# extio.net
KiCad netlist of a schematic drawn in Altium Designer
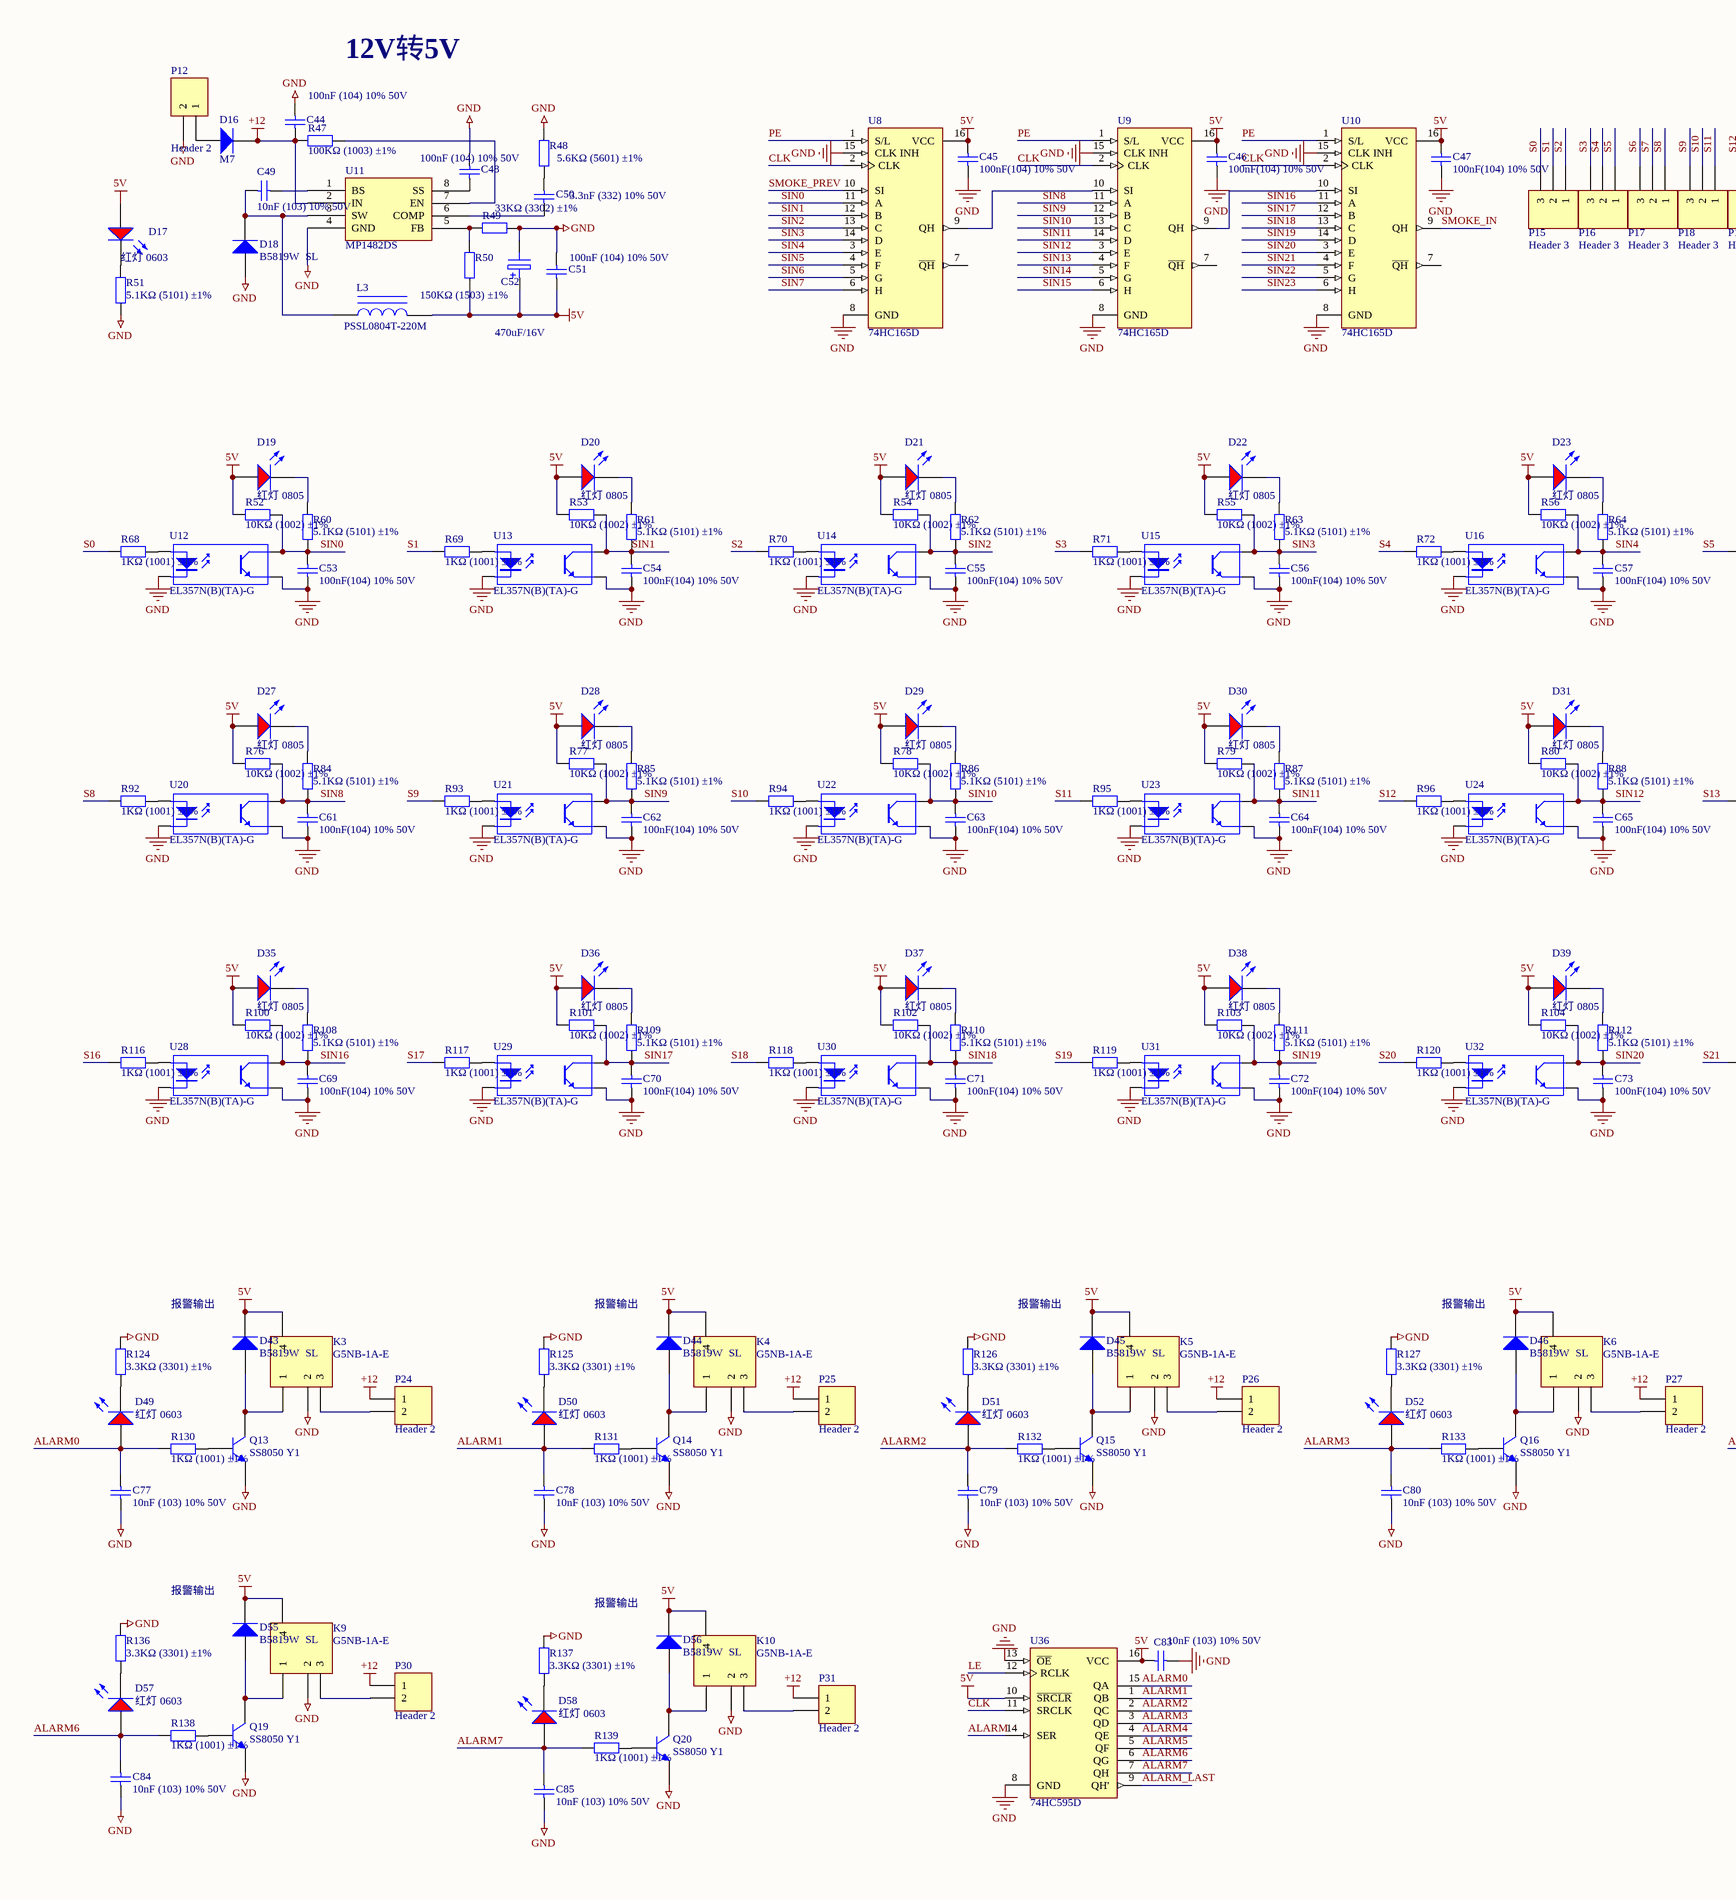
[diagram p0: extio.SchDoc, left]
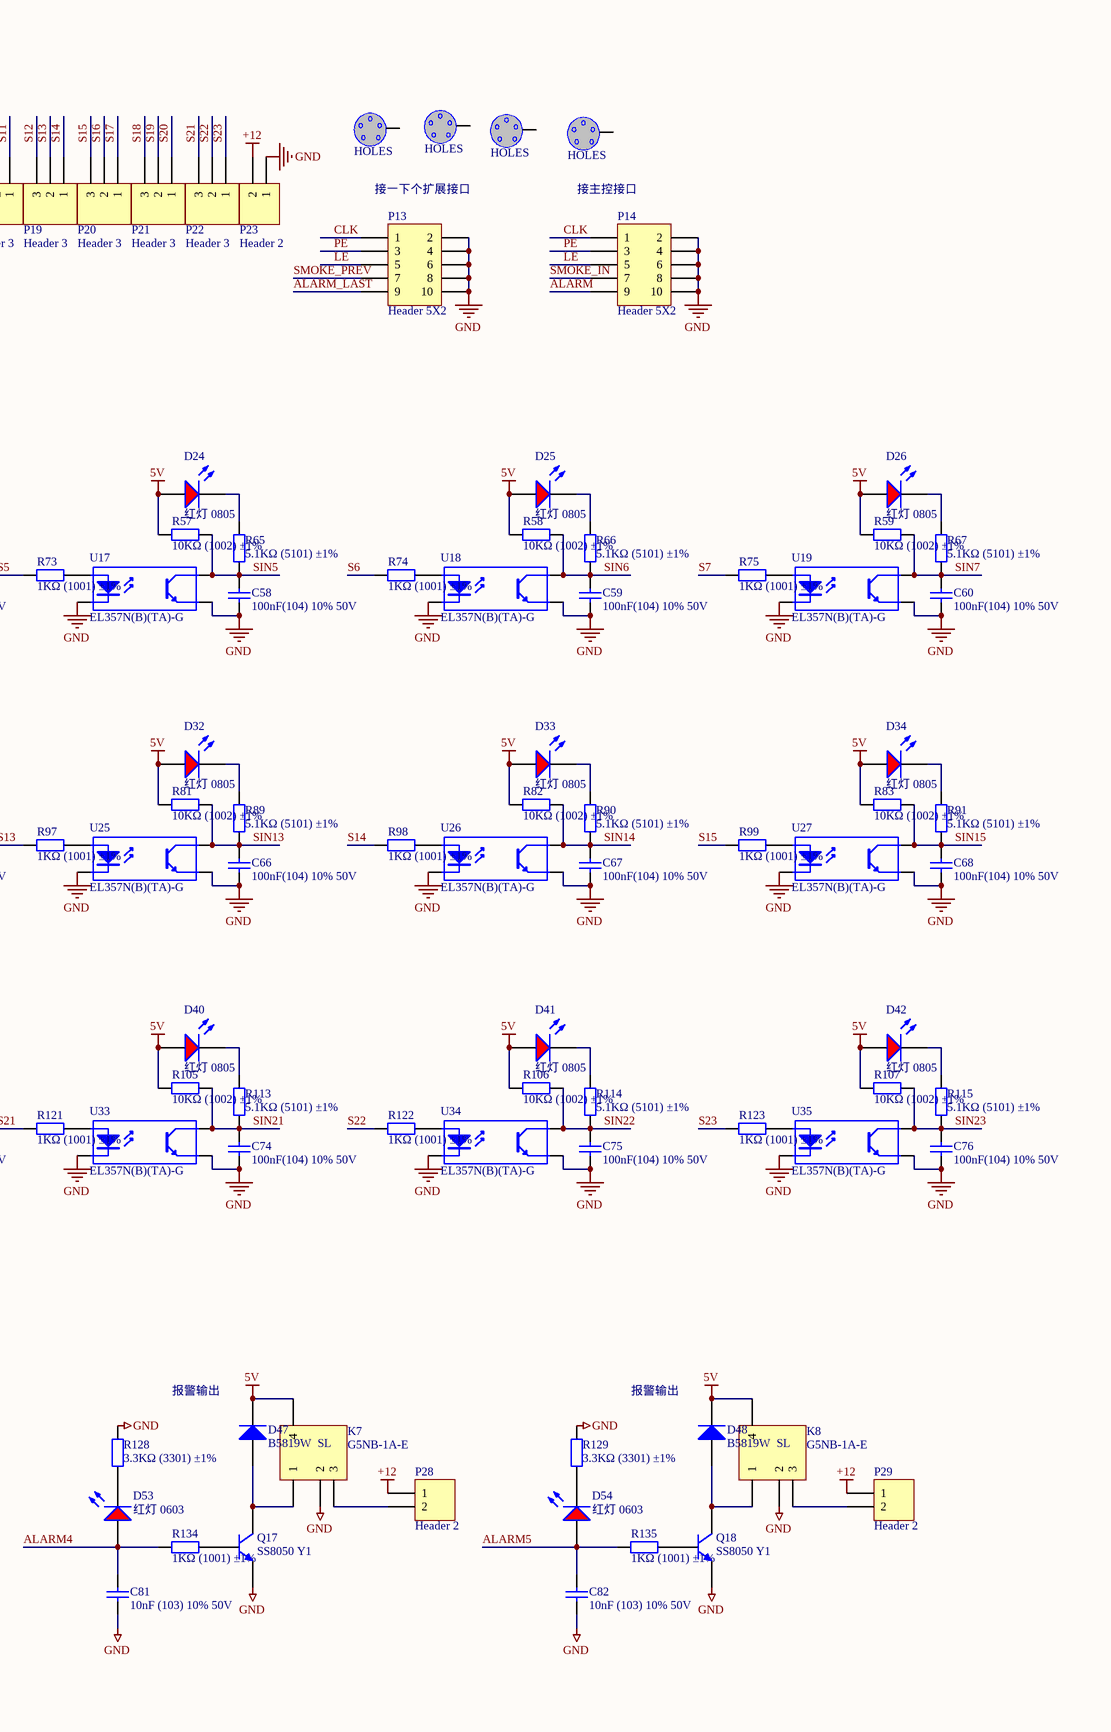
[diagram p1: extio.SchDoc, right]

(export (version "E")
  (design (tool "Eeschema 10.0.6"))
  (components
    (comp (ref "C44")
      (value "100nF (104) 10% 50V")
      (footprint "0603_C")
      (description "贴片电容")
      (libsource (lib "Cap") (part "0603 100nF (104) 10% 50V"))
    )
    (comp (ref "C45")
      (value "100nF(104) 10% 50V")
      (footprint "0805_C")
      (description "贴片电容")
      (libsource (lib "Cap") (part "0805 100nF(104) 10% 50V"))
    )
    (comp (ref "C46")
      (value "100nF(104) 10% 50V")
      (footprint "0805_C")
      (description "贴片电容")
      (libsource (lib "Cap") (part "0805 100nF(104) 10% 50V"))
    )
    (comp (ref "C47")
      (value "100nF(104) 10% 50V")
      (footprint "0805_C")
      (description "贴片电容")
      (libsource (lib "Cap") (part "0805 100nF(104) 10% 50V"))
    )
    (comp (ref "C48")
      (value "100nF (104) 10% 50V")
      (footprint "0603_C")
      (description "贴片电容")
      (libsource (lib "Cap") (part "0603 100nF (104) 10% 50V"))
    )
    (comp (ref "C49")
      (value "10nF (103) 10% 50V")
      (footprint "0603_C")
      (description "贴片电容")
      (libsource (lib "Cap") (part "0603 10nF (103) 10% 50V"))
    )
    (comp (ref "C50")
      (value "3.3nF (332) 10% 50V")
      (footprint "0603_C")
      (description "贴片电容")
      (libsource (lib "Cap") (part "0603 3.3nF (332) 10% 50V"))
    )
    (comp (ref "C51")
      (value "100nF (104) 10% 50V")
      (footprint "0603_C")
      (description "贴片电容")
      (libsource (lib "Cap") (part "0603 100nF (104) 10% 50V"))
    )
    (comp (ref "C52")
      (value "470uF/16V")
      (footprint "153CLV-0810")
      (description "Electrolytic Capacitor")
      (libsource (lib "*") (part "ELECTRO1"))
    )
    (comp (ref "C53")
      (value "100nF(104) 10% 50V")
      (footprint "0805_C")
      (description "贴片电容")
      (libsource (lib "Cap") (part "0805 100nF(104) 10% 50V"))
    )
    (comp (ref "C54")
      (value "100nF(104) 10% 50V")
      (footprint "0805_C")
      (description "贴片电容")
      (libsource (lib "Cap") (part "0805 100nF(104) 10% 50V"))
    )
    (comp (ref "C55")
      (value "100nF(104) 10% 50V")
      (footprint "0805_C")
      (description "贴片电容")
      (libsource (lib "Cap") (part "0805 100nF(104) 10% 50V"))
    )
    (comp (ref "C56")
      (value "100nF(104) 10% 50V")
      (footprint "0805_C")
      (description "贴片电容")
      (libsource (lib "Cap") (part "0805 100nF(104) 10% 50V"))
    )
    (comp (ref "C57")
      (value "100nF(104) 10% 50V")
      (footprint "0805_C")
      (description "贴片电容")
      (libsource (lib "Cap") (part "0805 100nF(104) 10% 50V"))
    )
    (comp (ref "C58")
      (value "100nF(104) 10% 50V")
      (footprint "0805_C")
      (description "贴片电容")
      (libsource (lib "Cap") (part "0805 100nF(104) 10% 50V"))
    )
    (comp (ref "C59")
      (value "100nF(104) 10% 50V")
      (footprint "0805_C")
      (description "贴片电容")
      (libsource (lib "Cap") (part "0805 100nF(104) 10% 50V"))
    )
    (comp (ref "C60")
      (value "100nF(104) 10% 50V")
      (footprint "0805_C")
      (description "贴片电容")
      (libsource (lib "Cap") (part "0805 100nF(104) 10% 50V"))
    )
    (comp (ref "C61")
      (value "100nF(104) 10% 50V")
      (footprint "0805_C")
      (description "贴片电容")
      (libsource (lib "Cap") (part "0805 100nF(104) 10% 50V"))
    )
    (comp (ref "C62")
      (value "100nF(104) 10% 50V")
      (footprint "0805_C")
      (description "贴片电容")
      (libsource (lib "Cap") (part "0805 100nF(104) 10% 50V"))
    )
    (comp (ref "C63")
      (value "100nF(104) 10% 50V")
      (footprint "0805_C")
      (description "贴片电容")
      (libsource (lib "Cap") (part "0805 100nF(104) 10% 50V"))
    )
    (comp (ref "C64")
      (value "100nF(104) 10% 50V")
      (footprint "0805_C")
      (description "贴片电容")
      (libsource (lib "Cap") (part "0805 100nF(104) 10% 50V"))
    )
    (comp (ref "C65")
      (value "100nF(104) 10% 50V")
      (footprint "0805_C")
      (description "贴片电容")
      (libsource (lib "Cap") (part "0805 100nF(104) 10% 50V"))
    )
    (comp (ref "C66")
      (value "100nF(104) 10% 50V")
      (footprint "0805_C")
      (description "贴片电容")
      (libsource (lib "Cap") (part "0805 100nF(104) 10% 50V"))
    )
    (comp (ref "C67")
      (value "100nF(104) 10% 50V")
      (footprint "0805_C")
      (description "贴片电容")
      (libsource (lib "Cap") (part "0805 100nF(104) 10% 50V"))
    )
    (comp (ref "C68")
      (value "100nF(104) 10% 50V")
      (footprint "0805_C")
      (description "贴片电容")
      (libsource (lib "Cap") (part "0805 100nF(104) 10% 50V"))
    )
    (comp (ref "C69")
      (value "100nF(104) 10% 50V")
      (footprint "0805_C")
      (description "贴片电容")
      (libsource (lib "Cap") (part "0805 100nF(104) 10% 50V"))
    )
    (comp (ref "C70")
      (value "100nF(104) 10% 50V")
      (footprint "0805_C")
      (description "贴片电容")
      (libsource (lib "Cap") (part "0805 100nF(104) 10% 50V"))
    )
    (comp (ref "C71")
      (value "100nF(104) 10% 50V")
      (footprint "0805_C")
      (description "贴片电容")
      (libsource (lib "Cap") (part "0805 100nF(104) 10% 50V"))
    )
    (comp (ref "C72")
      (value "100nF(104) 10% 50V")
      (footprint "0805_C")
      (description "贴片电容")
      (libsource (lib "Cap") (part "0805 100nF(104) 10% 50V"))
    )
    (comp (ref "C73")
      (value "100nF(104) 10% 50V")
      (footprint "0805_C")
      (description "贴片电容")
      (libsource (lib "Cap") (part "0805 100nF(104) 10% 50V"))
    )
    (comp (ref "C74")
      (value "100nF(104) 10% 50V")
      (footprint "0805_C")
      (description "贴片电容")
      (libsource (lib "Cap") (part "0805 100nF(104) 10% 50V"))
    )
    (comp (ref "C75")
      (value "100nF(104) 10% 50V")
      (footprint "0805_C")
      (description "贴片电容")
      (libsource (lib "Cap") (part "0805 100nF(104) 10% 50V"))
    )
    (comp (ref "C76")
      (value "100nF(104) 10% 50V")
      (footprint "0805_C")
      (description "贴片电容")
      (libsource (lib "Cap") (part "0805 100nF(104) 10% 50V"))
    )
    (comp (ref "C77")
      (value "10nF (103) 10% 50V")
      (footprint "0603_C")
      (description "贴片电容")
      (libsource (lib "Cap") (part "0603 10nF (103) 10% 50V"))
    )
    (comp (ref "C78")
      (value "10nF (103) 10% 50V")
      (footprint "0603_C")
      (description "贴片电容")
      (libsource (lib "Cap") (part "0603 10nF (103) 10% 50V"))
    )
    (comp (ref "C79")
      (value "10nF (103) 10% 50V")
      (footprint "0603_C")
      (description "贴片电容")
      (libsource (lib "Cap") (part "0603 10nF (103) 10% 50V"))
    )
    (comp (ref "C80")
      (value "10nF (103) 10% 50V")
      (footprint "0603_C")
      (description "贴片电容")
      (libsource (lib "Cap") (part "0603 10nF (103) 10% 50V"))
    )
    (comp (ref "C81")
      (value "10nF (103) 10% 50V")
      (footprint "0603_C")
      (description "贴片电容")
      (libsource (lib "Cap") (part "0603 10nF (103) 10% 50V"))
    )
    (comp (ref "C82")
      (value "10nF (103) 10% 50V")
      (footprint "0603_C")
      (description "贴片电容")
      (libsource (lib "Cap") (part "0603 10nF (103) 10% 50V"))
    )
    (comp (ref "C83")
      (value "10nF (103) 10% 50V")
      (footprint "0603_C")
      (description "贴片电容")
      (libsource (lib "Cap") (part "0603 10nF (103) 10% 50V"))
    )
    (comp (ref "C84")
      (value "10nF (103) 10% 50V")
      (footprint "0603_C")
      (description "贴片电容")
      (libsource (lib "Cap") (part "0603 10nF (103) 10% 50V"))
    )
    (comp (ref "C85")
      (value "10nF (103) 10% 50V")
      (footprint "0603_C")
      (description "贴片电容")
      (libsource (lib "Cap") (part "0603 10nF (103) 10% 50V"))
    )
    (comp (ref "D16")
      (value "M7")
      (footprint "SMA(DO-214AC)_S1")
      (description "二极管")
      (libsource (lib "Diode") (part "SMA(DO-214AC) M7"))
    )
    (comp (ref "D17")
      (value "红灯 0603")
      (footprint "0603_LED_S1")
      (description "发光二极管")
      (libsource (lib "LED") (part "0603 红灯"))
    )
    (comp (ref "D18")
      (value "B5819W  SL")
      (footprint "SOD-123")
      (description "肖特基二极管")
      (libsource (lib "Diode") (part "SOD-123 B5819W  SL"))
    )
    (comp (ref "D19")
      (value "红灯 0805")
      (footprint "0805_LED_S1")
      (description "发光二极管")
      (libsource (lib "LED") (part "0805 红灯"))
    )
    (comp (ref "D20")
      (value "红灯 0805")
      (footprint "0805_LED_S1")
      (description "发光二极管")
      (libsource (lib "LED") (part "0805 红灯"))
    )
    (comp (ref "D21")
      (value "红灯 0805")
      (footprint "0805_LED_S1")
      (description "发光二极管")
      (libsource (lib "LED") (part "0805 红灯"))
    )
    (comp (ref "D22")
      (value "红灯 0805")
      (footprint "0805_LED_S1")
      (description "发光二极管")
      (libsource (lib "LED") (part "0805 红灯"))
    )
    (comp (ref "D23")
      (value "红灯 0805")
      (footprint "0805_LED_S1")
      (description "发光二极管")
      (libsource (lib "LED") (part "0805 红灯"))
    )
    (comp (ref "D24")
      (value "红灯 0805")
      (footprint "0805_LED_S1")
      (description "发光二极管")
      (libsource (lib "LED") (part "0805 红灯"))
    )
    (comp (ref "D25")
      (value "红灯 0805")
      (footprint "0805_LED_S1")
      (description "发光二极管")
      (libsource (lib "LED") (part "0805 红灯"))
    )
    (comp (ref "D26")
      (value "红灯 0805")
      (footprint "0805_LED_S1")
      (description "发光二极管")
      (libsource (lib "LED") (part "0805 红灯"))
    )
    (comp (ref "D27")
      (value "红灯 0805")
      (footprint "0805_LED_S1")
      (description "发光二极管")
      (libsource (lib "LED") (part "0805 红灯"))
    )
    (comp (ref "D28")
      (value "红灯 0805")
      (footprint "0805_LED_S1")
      (description "发光二极管")
      (libsource (lib "LED") (part "0805 红灯"))
    )
    (comp (ref "D29")
      (value "红灯 0805")
      (footprint "0805_LED_S1")
      (description "发光二极管")
      (libsource (lib "LED") (part "0805 红灯"))
    )
    (comp (ref "D30")
      (value "红灯 0805")
      (footprint "0805_LED_S1")
      (description "发光二极管")
      (libsource (lib "LED") (part "0805 红灯"))
    )
    (comp (ref "D31")
      (value "红灯 0805")
      (footprint "0805_LED_S1")
      (description "发光二极管")
      (libsource (lib "LED") (part "0805 红灯"))
    )
    (comp (ref "D32")
      (value "红灯 0805")
      (footprint "0805_LED_S1")
      (description "发光二极管")
      (libsource (lib "LED") (part "0805 红灯"))
    )
    (comp (ref "D33")
      (value "红灯 0805")
      (footprint "0805_LED_S1")
      (description "发光二极管")
      (libsource (lib "LED") (part "0805 红灯"))
    )
    (comp (ref "D34")
      (value "红灯 0805")
      (footprint "0805_LED_S1")
      (description "发光二极管")
      (libsource (lib "LED") (part "0805 红灯"))
    )
    (comp (ref "D35")
      (value "红灯 0805")
      (footprint "0805_LED_S1")
      (description "发光二极管")
      (libsource (lib "LED") (part "0805 红灯"))
    )
    (comp (ref "D36")
      (value "红灯 0805")
      (footprint "0805_LED_S1")
      (description "发光二极管")
      (libsource (lib "LED") (part "0805 红灯"))
    )
    (comp (ref "D37")
      (value "红灯 0805")
      (footprint "0805_LED_S1")
      (description "发光二极管")
      (libsource (lib "LED") (part "0805 红灯"))
    )
    (comp (ref "D38")
      (value "红灯 0805")
      (footprint "0805_LED_S1")
      (description "发光二极管")
      (libsource (lib "LED") (part "0805 红灯"))
    )
    (comp (ref "D39")
      (value "红灯 0805")
      (footprint "0805_LED_S1")
      (description "发光二极管")
      (libsource (lib "LED") (part "0805 红灯"))
    )
    (comp (ref "D40")
      (value "红灯 0805")
      (footprint "0805_LED_S1")
      (description "发光二极管")
      (libsource (lib "LED") (part "0805 红灯"))
    )
    (comp (ref "D41")
      (value "红灯 0805")
      (footprint "0805_LED_S1")
      (description "发光二极管")
      (libsource (lib "LED") (part "0805 红灯"))
    )
    (comp (ref "D42")
      (value "红灯 0805")
      (footprint "0805_LED_S1")
      (description "发光二极管")
      (libsource (lib "LED") (part "0805 红灯"))
    )
    (comp (ref "D43")
      (value "B5819W  SL")
      (footprint "SOD-123")
      (description "肖特基二极管")
      (libsource (lib "Diode") (part "SOD-123 B5819W  SL"))
    )
    (comp (ref "D44")
      (value "B5819W  SL")
      (footprint "SOD-123")
      (description "肖特基二极管")
      (libsource (lib "Diode") (part "SOD-123 B5819W  SL"))
    )
    (comp (ref "D45")
      (value "B5819W  SL")
      (footprint "SOD-123")
      (description "肖特基二极管")
      (libsource (lib "Diode") (part "SOD-123 B5819W  SL"))
    )
    (comp (ref "D46")
      (value "B5819W  SL")
      (footprint "SOD-123")
      (description "肖特基二极管")
      (libsource (lib "Diode") (part "SOD-123 B5819W  SL"))
    )
    (comp (ref "D47")
      (value "B5819W  SL")
      (footprint "SOD-123")
      (description "肖特基二极管")
      (libsource (lib "Diode") (part "SOD-123 B5819W  SL"))
    )
    (comp (ref "D48")
      (value "B5819W  SL")
      (footprint "SOD-123")
      (description "肖特基二极管")
      (libsource (lib "Diode") (part "SOD-123 B5819W  SL"))
    )
    (comp (ref "D49")
      (value "红灯 0603")
      (footprint "0603_LED_S1")
      (description "发光二极管")
      (libsource (lib "LED") (part "0603 红灯"))
    )
    (comp (ref "D50")
      (value "红灯 0603")
      (footprint "0603_LED_S1")
      (description "发光二极管")
      (libsource (lib "LED") (part "0603 红灯"))
    )
    (comp (ref "D51")
      (value "红灯 0603")
      (footprint "0603_LED_S1")
      (description "发光二极管")
      (libsource (lib "LED") (part "0603 红灯"))
    )
    (comp (ref "D52")
      (value "红灯 0603")
      (footprint "0603_LED_S1")
      (description "发光二极管")
      (libsource (lib "LED") (part "0603 红灯"))
    )
    (comp (ref "D53")
      (value "红灯 0603")
      (footprint "0603_LED_S1")
      (description "发光二极管")
      (libsource (lib "LED") (part "0603 红灯"))
    )
    (comp (ref "D54")
      (value "红灯 0603")
      (footprint "0603_LED_S1")
      (description "发光二极管")
      (libsource (lib "LED") (part "0603 红灯"))
    )
    (comp (ref "D55")
      (value "B5819W  SL")
      (footprint "SOD-123")
      (description "肖特基二极管")
      (libsource (lib "Diode") (part "SOD-123 B5819W  SL"))
    )
    (comp (ref "D56")
      (value "B5819W  SL")
      (footprint "SOD-123")
      (description "肖特基二极管")
      (libsource (lib "Diode") (part "SOD-123 B5819W  SL"))
    )
    (comp (ref "D57")
      (value "红灯 0603")
      (footprint "0603_LED_S1")
      (description "发光二极管")
      (libsource (lib "LED") (part "0603 红灯"))
    )
    (comp (ref "D58")
      (value "红灯 0603")
      (footprint "0603_LED_S1")
      (description "发光二极管")
      (libsource (lib "LED") (part "0603 红灯"))
    )
    (comp (ref "HOLES1")
      (value "HOLES")
      (footprint "HOLES")
      (description "holes for fastening")
      (libsource (lib "*") (part "HOLES"))
    )
    (comp (ref "HOLES2")
      (value "HOLES")
      (footprint "HOLES")
      (description "holes for fastening")
      (libsource (lib "*") (part "HOLES"))
    )
    (comp (ref "HOLES3")
      (value "HOLES")
      (footprint "HOLES")
      (description "holes for fastening")
      (libsource (lib "*") (part "HOLES"))
    )
    (comp (ref "HOLES4")
      (value "HOLES")
      (footprint "HOLES")
      (description "holes for fastening")
      (libsource (lib "*") (part "HOLES"))
    )
    (comp (ref "K3") (value "G5NB-1A-E") (footprint "G5NB-1A") (libsource (lib "*") (part "G5NB-1A-E")))
    (comp (ref "K4") (value "G5NB-1A-E") (footprint "G5NB-1A") (libsource (lib "*") (part "G5NB-1A-E")))
    (comp (ref "K5") (value "G5NB-1A-E") (footprint "G5NB-1A") (libsource (lib "*") (part "G5NB-1A-E")))
    (comp (ref "K6") (value "G5NB-1A-E") (footprint "G5NB-1A") (libsource (lib "*") (part "G5NB-1A-E")))
    (comp (ref "K7") (value "G5NB-1A-E") (footprint "G5NB-1A") (libsource (lib "*") (part "G5NB-1A-E")))
    (comp (ref "K8") (value "G5NB-1A-E") (footprint "G5NB-1A") (libsource (lib "*") (part "G5NB-1A-E")))
    (comp (ref "K9") (value "G5NB-1A-E") (footprint "G5NB-1A") (libsource (lib "*") (part "G5NB-1A-E")))
    (comp (ref "K10") (value "G5NB-1A-E") (footprint "G5NB-1A") (libsource (lib "*") (part "G5NB-1A-E")))
    (comp (ref "L3") (value "PSSL0804T-220M") (footprint "L7-8") (libsource (lib "*") (part "INDUCTOR IRON")))
    (comp (ref "P12")
      (value "Header 2")
      (footprint "KF396-2P")
      (description "Header, 2-Pin")
      (fields (field (name "PUBLISHER") "Altium Limited"))
      (libsource (lib "Miscellaneous Connectors") (part "Header 2"))
    )
    (comp (ref "P13")
      (value "Header 5X2")
      (footprint "ML10")
      (description "Header, 5-Pin, Dual row")
      (fields (field (name "PUBLISHER") "Altium Limited"))
      (libsource (lib "Miscellaneous Connectors") (part "Header 5X2"))
    )
    (comp (ref "P14")
      (value "Header 5X2")
      (footprint "ML10")
      (description "Header, 5-Pin, Dual row")
      (fields (field (name "PUBLISHER") "Altium Limited"))
      (libsource (lib "Miscellaneous Connectors") (part "Header 5X2"))
    )
    (comp (ref "P15")
      (value "Header 3")
      (footprint "KF396-3P")
      (description "Header, 3-Pin")
      (fields (field (name "PUBLISHER") "Altium Limited"))
      (libsource (lib "Miscellaneous Connectors") (part "Header 3"))
    )
    (comp (ref "P16")
      (value "Header 3")
      (footprint "KF396-3P")
      (description "Header, 3-Pin")
      (fields (field (name "PUBLISHER") "Altium Limited"))
      (libsource (lib "Miscellaneous Connectors") (part "Header 3"))
    )
    (comp (ref "P17")
      (value "Header 3")
      (footprint "KF396-3P")
      (description "Header, 3-Pin")
      (fields (field (name "PUBLISHER") "Altium Limited"))
      (libsource (lib "Miscellaneous Connectors") (part "Header 3"))
    )
    (comp (ref "P18")
      (value "Header 3")
      (footprint "KF396-3P")
      (description "Header, 3-Pin")
      (fields (field (name "PUBLISHER") "Altium Limited"))
      (libsource (lib "Miscellaneous Connectors") (part "Header 3"))
    )
    (comp (ref "P19")
      (value "Header 3")
      (footprint "KF396-3P")
      (description "Header, 3-Pin")
      (fields (field (name "PUBLISHER") "Altium Limited"))
      (libsource (lib "Miscellaneous Connectors") (part "Header 3"))
    )
    (comp (ref "P20")
      (value "Header 3")
      (footprint "KF396-3P")
      (description "Header, 3-Pin")
      (fields (field (name "PUBLISHER") "Altium Limited"))
      (libsource (lib "Miscellaneous Connectors") (part "Header 3"))
    )
    (comp (ref "P21")
      (value "Header 3")
      (footprint "KF396-3P")
      (description "Header, 3-Pin")
      (fields (field (name "PUBLISHER") "Altium Limited"))
      (libsource (lib "Miscellaneous Connectors") (part "Header 3"))
    )
    (comp (ref "P22")
      (value "Header 3")
      (footprint "KF396-3P")
      (description "Header, 3-Pin")
      (fields (field (name "PUBLISHER") "Altium Limited"))
      (libsource (lib "Miscellaneous Connectors") (part "Header 3"))
    )
    (comp (ref "P23")
      (value "Header 2")
      (footprint "KF396-2P")
      (description "Header, 2-Pin")
      (fields (field (name "PUBLISHER") "Altium Limited"))
      (libsource (lib "") (part "Header 2_1"))
    )
    (comp (ref "P24")
      (value "Header 2")
      (footprint "KF396-2P")
      (description "Header, 2-Pin")
      (fields (field (name "PUBLISHER") "Altium Limited"))
      (libsource (lib "Miscellaneous Connectors") (part "Header 2"))
    )
    (comp (ref "P25")
      (value "Header 2")
      (footprint "KF396-2P")
      (description "Header, 2-Pin")
      (fields (field (name "PUBLISHER") "Altium Limited"))
      (libsource (lib "Miscellaneous Connectors") (part "Header 2"))
    )
    (comp (ref "P26")
      (value "Header 2")
      (footprint "KF396-2P")
      (description "Header, 2-Pin")
      (fields (field (name "PUBLISHER") "Altium Limited"))
      (libsource (lib "Miscellaneous Connectors") (part "Header 2"))
    )
    (comp (ref "P27")
      (value "Header 2")
      (footprint "KF396-2P")
      (description "Header, 2-Pin")
      (fields (field (name "PUBLISHER") "Altium Limited"))
      (libsource (lib "Miscellaneous Connectors") (part "Header 2"))
    )
    (comp (ref "P28")
      (value "Header 2")
      (footprint "KF396-2P")
      (description "Header, 2-Pin")
      (fields (field (name "PUBLISHER") "Altium Limited"))
      (libsource (lib "Miscellaneous Connectors") (part "Header 2"))
    )
    (comp (ref "P29")
      (value "Header 2")
      (footprint "KF396-2P")
      (description "Header, 2-Pin")
      (fields (field (name "PUBLISHER") "Altium Limited"))
      (libsource (lib "Miscellaneous Connectors") (part "Header 2"))
    )
    (comp (ref "P30")
      (value "Header 2")
      (footprint "KF396-2P")
      (description "Header, 2-Pin")
      (fields (field (name "PUBLISHER") "Altium Limited"))
      (libsource (lib "Miscellaneous Connectors") (part "Header 2"))
    )
    (comp (ref "P31")
      (value "Header 2")
      (footprint "KF396-2P")
      (description "Header, 2-Pin")
      (fields (field (name "PUBLISHER") "Altium Limited"))
      (libsource (lib "Miscellaneous Connectors") (part "Header 2"))
    )
    (comp (ref "Q13")
      (value "SS8050 Y1")
      (footprint "SOT-23(SOT-23-3)")
      (description "三极管")
      (libsource (lib "Transistor_NPN") (part "SOT-23 SS8050 Y1"))
    )
    (comp (ref "Q14")
      (value "SS8050 Y1")
      (footprint "SOT-23(SOT-23-3)")
      (description "三极管")
      (libsource (lib "Transistor_NPN") (part "SOT-23 SS8050 Y1"))
    )
    (comp (ref "Q15")
      (value "SS8050 Y1")
      (footprint "SOT-23(SOT-23-3)")
      (description "三极管")
      (libsource (lib "Transistor_NPN") (part "SOT-23 SS8050 Y1"))
    )
    (comp (ref "Q16")
      (value "SS8050 Y1")
      (footprint "SOT-23(SOT-23-3)")
      (description "三极管")
      (libsource (lib "Transistor_NPN") (part "SOT-23 SS8050 Y1"))
    )
    (comp (ref "Q17")
      (value "SS8050 Y1")
      (footprint "SOT-23(SOT-23-3)")
      (description "三极管")
      (libsource (lib "Transistor_NPN") (part "SOT-23 SS8050 Y1"))
    )
    (comp (ref "Q18")
      (value "SS8050 Y1")
      (footprint "SOT-23(SOT-23-3)")
      (description "三极管")
      (libsource (lib "Transistor_NPN") (part "SOT-23 SS8050 Y1"))
    )
    (comp (ref "Q19")
      (value "SS8050 Y1")
      (footprint "SOT-23(SOT-23-3)")
      (description "三极管")
      (libsource (lib "Transistor_NPN") (part "SOT-23 SS8050 Y1"))
    )
    (comp (ref "Q20")
      (value "SS8050 Y1")
      (footprint "SOT-23(SOT-23-3)")
      (description "三极管")
      (libsource (lib "Transistor_NPN") (part "SOT-23 SS8050 Y1"))
    )
    (comp (ref "R47")
      (value "100KΩ (1003) ±1%")
      (footprint "0603_R")
      (description "贴片电阻")
      (libsource (lib "RES") (part "0603 100KΩ (1003) 1%"))
    )
    (comp (ref "R48")
      (value "5.6KΩ (5601) ±1%")
      (footprint "0603_R")
      (description "贴片电阻")
      (libsource (lib "RES") (part "0603 5.6KΩ (5601) 1%"))
    )
    (comp (ref "R49")
      (value "33KΩ (3302) ±1%")
      (footprint "0603_R")
      (description "贴片电阻")
      (libsource (lib "RES") (part "0603 33KΩ (3302) 1%"))
    )
    (comp (ref "R50")
      (value "150KΩ (1503) ±1%")
      (footprint "0603_R")
      (description "贴片电阻")
      (libsource (lib "RES") (part "0603 150KΩ (1503) 1%"))
    )
    (comp (ref "R51")
      (value "5.1KΩ (5101) ±1%")
      (footprint "0805_R")
      (description "贴片电阻")
      (libsource (lib "RES") (part "0805 5.1KΩ (5101) 1%"))
    )
    (comp (ref "R52")
      (value "10KΩ (1002) ±1%")
      (footprint "0805_R")
      (description "贴片电阻")
      (libsource (lib "RES") (part "0805 10KΩ (1002) 1%"))
    )
    (comp (ref "R53")
      (value "10KΩ (1002) ±1%")
      (footprint "0805_R")
      (description "贴片电阻")
      (libsource (lib "RES") (part "0805 10KΩ (1002) 1%"))
    )
    (comp (ref "R54")
      (value "10KΩ (1002) ±1%")
      (footprint "0805_R")
      (description "贴片电阻")
      (libsource (lib "RES") (part "0805 10KΩ (1002) 1%"))
    )
    (comp (ref "R55")
      (value "10KΩ (1002) ±1%")
      (footprint "0805_R")
      (description "贴片电阻")
      (libsource (lib "RES") (part "0805 10KΩ (1002) 1%"))
    )
    (comp (ref "R56")
      (value "10KΩ (1002) ±1%")
      (footprint "0805_R")
      (description "贴片电阻")
      (libsource (lib "RES") (part "0805 10KΩ (1002) 1%"))
    )
    (comp (ref "R57")
      (value "10KΩ (1002) ±1%")
      (footprint "0805_R")
      (description "贴片电阻")
      (libsource (lib "RES") (part "0805 10KΩ (1002) 1%"))
    )
    (comp (ref "R58")
      (value "10KΩ (1002) ±1%")
      (footprint "0805_R")
      (description "贴片电阻")
      (libsource (lib "RES") (part "0805 10KΩ (1002) 1%"))
    )
    (comp (ref "R59")
      (value "10KΩ (1002) ±1%")
      (footprint "0805_R")
      (description "贴片电阻")
      (libsource (lib "RES") (part "0805 10KΩ (1002) 1%"))
    )
    (comp (ref "R60")
      (value "5.1KΩ (5101) ±1%")
      (footprint "0805_R")
      (description "贴片电阻")
      (libsource (lib "RES") (part "0805 5.1KΩ (5101) 1%"))
    )
    (comp (ref "R61")
      (value "5.1KΩ (5101) ±1%")
      (footprint "0805_R")
      (description "贴片电阻")
      (libsource (lib "RES") (part "0805 5.1KΩ (5101) 1%"))
    )
    (comp (ref "R62")
      (value "5.1KΩ (5101) ±1%")
      (footprint "0805_R")
      (description "贴片电阻")
      (libsource (lib "RES") (part "0805 5.1KΩ (5101) 1%"))
    )
    (comp (ref "R63")
      (value "5.1KΩ (5101) ±1%")
      (footprint "0805_R")
      (description "贴片电阻")
      (libsource (lib "RES") (part "0805 5.1KΩ (5101) 1%"))
    )
    (comp (ref "R64")
      (value "5.1KΩ (5101) ±1%")
      (footprint "0805_R")
      (description "贴片电阻")
      (libsource (lib "RES") (part "0805 5.1KΩ (5101) 1%"))
    )
    (comp (ref "R65")
      (value "5.1KΩ (5101) ±1%")
      (footprint "0805_R")
      (description "贴片电阻")
      (libsource (lib "RES") (part "0805 5.1KΩ (5101) 1%"))
    )
    (comp (ref "R66")
      (value "5.1KΩ (5101) ±1%")
      (footprint "0805_R")
      (description "贴片电阻")
      (libsource (lib "RES") (part "0805 5.1KΩ (5101) 1%"))
    )
    (comp (ref "R67")
      (value "5.1KΩ (5101) ±1%")
      (footprint "0805_R")
      (description "贴片电阻")
      (libsource (lib "RES") (part "0805 5.1KΩ (5101) 1%"))
    )
    (comp (ref "R68")
      (value "1KΩ (1001) ±1%")
      (footprint "0805_R")
      (description "贴片电阻")
      (libsource (lib "RES") (part "0805 1KΩ (1001) 1%"))
    )
    (comp (ref "R69")
      (value "1KΩ (1001) ±1%")
      (footprint "0805_R")
      (description "贴片电阻")
      (libsource (lib "RES") (part "0805 1KΩ (1001) 1%"))
    )
    (comp (ref "R70")
      (value "1KΩ (1001) ±1%")
      (footprint "0805_R")
      (description "贴片电阻")
      (libsource (lib "RES") (part "0805 1KΩ (1001) 1%"))
    )
    (comp (ref "R71")
      (value "1KΩ (1001) ±1%")
      (footprint "0805_R")
      (description "贴片电阻")
      (libsource (lib "RES") (part "0805 1KΩ (1001) 1%"))
    )
    (comp (ref "R72")
      (value "1KΩ (1001) ±1%")
      (footprint "0805_R")
      (description "贴片电阻")
      (libsource (lib "RES") (part "0805 1KΩ (1001) 1%"))
    )
    (comp (ref "R73")
      (value "1KΩ (1001) ±1%")
      (footprint "0805_R")
      (description "贴片电阻")
      (libsource (lib "RES") (part "0805 1KΩ (1001) 1%"))
    )
    (comp (ref "R74")
      (value "1KΩ (1001) ±1%")
      (footprint "0805_R")
      (description "贴片电阻")
      (libsource (lib "RES") (part "0805 1KΩ (1001) 1%"))
    )
    (comp (ref "R75")
      (value "1KΩ (1001) ±1%")
      (footprint "0805_R")
      (description "贴片电阻")
      (libsource (lib "RES") (part "0805 1KΩ (1001) 1%"))
    )
    (comp (ref "R76")
      (value "10KΩ (1002) ±1%")
      (footprint "0805_R")
      (description "贴片电阻")
      (libsource (lib "RES") (part "0805 10KΩ (1002) 1%"))
    )
    (comp (ref "R77")
      (value "10KΩ (1002) ±1%")
      (footprint "0805_R")
      (description "贴片电阻")
      (libsource (lib "RES") (part "0805 10KΩ (1002) 1%"))
    )
    (comp (ref "R78")
      (value "10KΩ (1002) ±1%")
      (footprint "0805_R")
      (description "贴片电阻")
      (libsource (lib "RES") (part "0805 10KΩ (1002) 1%"))
    )
    (comp (ref "R79")
      (value "10KΩ (1002) ±1%")
      (footprint "0805_R")
      (description "贴片电阻")
      (libsource (lib "RES") (part "0805 10KΩ (1002) 1%"))
    )
    (comp (ref "R80")
      (value "10KΩ (1002) ±1%")
      (footprint "0805_R")
      (description "贴片电阻")
      (libsource (lib "RES") (part "0805 10KΩ (1002) 1%"))
    )
    (comp (ref "R81")
      (value "10KΩ (1002) ±1%")
      (footprint "0805_R")
      (description "贴片电阻")
      (libsource (lib "RES") (part "0805 10KΩ (1002) 1%"))
    )
    (comp (ref "R82")
      (value "10KΩ (1002) ±1%")
      (footprint "0805_R")
      (description "贴片电阻")
      (libsource (lib "RES") (part "0805 10KΩ (1002) 1%"))
    )
    (comp (ref "R83")
      (value "10KΩ (1002) ±1%")
      (footprint "0805_R")
      (description "贴片电阻")
      (libsource (lib "RES") (part "0805 10KΩ (1002) 1%"))
    )
    (comp (ref "R84")
      (value "5.1KΩ (5101) ±1%")
      (footprint "0805_R")
      (description "贴片电阻")
      (libsource (lib "RES") (part "0805 5.1KΩ (5101) 1%"))
    )
    (comp (ref "R85")
      (value "5.1KΩ (5101) ±1%")
      (footprint "0805_R")
      (description "贴片电阻")
      (libsource (lib "RES") (part "0805 5.1KΩ (5101) 1%"))
    )
    (comp (ref "R86")
      (value "5.1KΩ (5101) ±1%")
      (footprint "0805_R")
      (description "贴片电阻")
      (libsource (lib "RES") (part "0805 5.1KΩ (5101) 1%"))
    )
    (comp (ref "R87")
      (value "5.1KΩ (5101) ±1%")
      (footprint "0805_R")
      (description "贴片电阻")
      (libsource (lib "RES") (part "0805 5.1KΩ (5101) 1%"))
    )
    (comp (ref "R88")
      (value "5.1KΩ (5101) ±1%")
      (footprint "0805_R")
      (description "贴片电阻")
      (libsource (lib "RES") (part "0805 5.1KΩ (5101) 1%"))
    )
    (comp (ref "R89")
      (value "5.1KΩ (5101) ±1%")
      (footprint "0805_R")
      (description "贴片电阻")
      (libsource (lib "RES") (part "0805 5.1KΩ (5101) 1%"))
    )
    (comp (ref "R90")
      (value "5.1KΩ (5101) ±1%")
      (footprint "0805_R")
      (description "贴片电阻")
      (libsource (lib "RES") (part "0805 5.1KΩ (5101) 1%"))
    )
    (comp (ref "R91")
      (value "5.1KΩ (5101) ±1%")
      (footprint "0805_R")
      (description "贴片电阻")
      (libsource (lib "RES") (part "0805 5.1KΩ (5101) 1%"))
    )
    (comp (ref "R92")
      (value "1KΩ (1001) ±1%")
      (footprint "0805_R")
      (description "贴片电阻")
      (libsource (lib "RES") (part "0805 1KΩ (1001) 1%"))
    )
    (comp (ref "R93")
      (value "1KΩ (1001) ±1%")
      (footprint "0805_R")
      (description "贴片电阻")
      (libsource (lib "RES") (part "0805 1KΩ (1001) 1%"))
    )
    (comp (ref "R94")
      (value "1KΩ (1001) ±1%")
      (footprint "0805_R")
      (description "贴片电阻")
      (libsource (lib "RES") (part "0805 1KΩ (1001) 1%"))
    )
    (comp (ref "R95")
      (value "1KΩ (1001) ±1%")
      (footprint "0805_R")
      (description "贴片电阻")
      (libsource (lib "RES") (part "0805 1KΩ (1001) 1%"))
    )
    (comp (ref "R96")
      (value "1KΩ (1001) ±1%")
      (footprint "0805_R")
      (description "贴片电阻")
      (libsource (lib "RES") (part "0805 1KΩ (1001) 1%"))
    )
    (comp (ref "R97")
      (value "1KΩ (1001) ±1%")
      (footprint "0805_R")
      (description "贴片电阻")
      (libsource (lib "RES") (part "0805 1KΩ (1001) 1%"))
    )
    (comp (ref "R98")
      (value "1KΩ (1001) ±1%")
      (footprint "0805_R")
      (description "贴片电阻")
      (libsource (lib "RES") (part "0805 1KΩ (1001) 1%"))
    )
    (comp (ref "R99")
      (value "1KΩ (1001) ±1%")
      (footprint "0805_R")
      (description "贴片电阻")
      (libsource (lib "RES") (part "0805 1KΩ (1001) 1%"))
    )
    (comp (ref "R100")
      (value "10KΩ (1002) ±1%")
      (footprint "0805_R")
      (description "贴片电阻")
      (libsource (lib "RES") (part "0805 10KΩ (1002) 1%"))
    )
    (comp (ref "R101")
      (value "10KΩ (1002) ±1%")
      (footprint "0805_R")
      (description "贴片电阻")
      (libsource (lib "RES") (part "0805 10KΩ (1002) 1%"))
    )
    (comp (ref "R102")
      (value "10KΩ (1002) ±1%")
      (footprint "0805_R")
      (description "贴片电阻")
      (libsource (lib "RES") (part "0805 10KΩ (1002) 1%"))
    )
    (comp (ref "R103")
      (value "10KΩ (1002) ±1%")
      (footprint "0805_R")
      (description "贴片电阻")
      (libsource (lib "RES") (part "0805 10KΩ (1002) 1%"))
    )
    (comp (ref "R104")
      (value "10KΩ (1002) ±1%")
      (footprint "0805_R")
      (description "贴片电阻")
      (libsource (lib "RES") (part "0805 10KΩ (1002) 1%"))
    )
    (comp (ref "R105")
      (value "10KΩ (1002) ±1%")
      (footprint "0805_R")
      (description "贴片电阻")
      (libsource (lib "RES") (part "0805 10KΩ (1002) 1%"))
    )
    (comp (ref "R106")
      (value "10KΩ (1002) ±1%")
      (footprint "0805_R")
      (description "贴片电阻")
      (libsource (lib "RES") (part "0805 10KΩ (1002) 1%"))
    )
    (comp (ref "R107")
      (value "10KΩ (1002) ±1%")
      (footprint "0805_R")
      (description "贴片电阻")
      (libsource (lib "RES") (part "0805 10KΩ (1002) 1%"))
    )
    (comp (ref "R108")
      (value "5.1KΩ (5101) ±1%")
      (footprint "0805_R")
      (description "贴片电阻")
      (libsource (lib "RES") (part "0805 5.1KΩ (5101) 1%"))
    )
    (comp (ref "R109")
      (value "5.1KΩ (5101) ±1%")
      (footprint "0805_R")
      (description "贴片电阻")
      (libsource (lib "RES") (part "0805 5.1KΩ (5101) 1%"))
    )
    (comp (ref "R110")
      (value "5.1KΩ (5101) ±1%")
      (footprint "0805_R")
      (description "贴片电阻")
      (libsource (lib "RES") (part "0805 5.1KΩ (5101) 1%"))
    )
    (comp (ref "R111")
      (value "5.1KΩ (5101) ±1%")
      (footprint "0805_R")
      (description "贴片电阻")
      (libsource (lib "RES") (part "0805 5.1KΩ (5101) 1%"))
    )
    (comp (ref "R112")
      (value "5.1KΩ (5101) ±1%")
      (footprint "0805_R")
      (description "贴片电阻")
      (libsource (lib "RES") (part "0805 5.1KΩ (5101) 1%"))
    )
    (comp (ref "R113")
      (value "5.1KΩ (5101) ±1%")
      (footprint "0805_R")
      (description "贴片电阻")
      (libsource (lib "RES") (part "0805 5.1KΩ (5101) 1%"))
    )
    (comp (ref "R114")
      (value "5.1KΩ (5101) ±1%")
      (footprint "0805_R")
      (description "贴片电阻")
      (libsource (lib "RES") (part "0805 5.1KΩ (5101) 1%"))
    )
    (comp (ref "R115")
      (value "5.1KΩ (5101) ±1%")
      (footprint "0805_R")
      (description "贴片电阻")
      (libsource (lib "RES") (part "0805 5.1KΩ (5101) 1%"))
    )
    (comp (ref "R116")
      (value "1KΩ (1001) ±1%")
      (footprint "0805_R")
      (description "贴片电阻")
      (libsource (lib "RES") (part "0805 1KΩ (1001) 1%"))
    )
    (comp (ref "R117")
      (value "1KΩ (1001) ±1%")
      (footprint "0805_R")
      (description "贴片电阻")
      (libsource (lib "RES") (part "0805 1KΩ (1001) 1%"))
    )
    (comp (ref "R118")
      (value "1KΩ (1001) ±1%")
      (footprint "0805_R")
      (description "贴片电阻")
      (libsource (lib "RES") (part "0805 1KΩ (1001) 1%"))
    )
    (comp (ref "R119")
      (value "1KΩ (1001) ±1%")
      (footprint "0805_R")
      (description "贴片电阻")
      (libsource (lib "RES") (part "0805 1KΩ (1001) 1%"))
    )
    (comp (ref "R120")
      (value "1KΩ (1001) ±1%")
      (footprint "0805_R")
      (description "贴片电阻")
      (libsource (lib "RES") (part "0805 1KΩ (1001) 1%"))
    )
    (comp (ref "R121")
      (value "1KΩ (1001) ±1%")
      (footprint "0805_R")
      (description "贴片电阻")
      (libsource (lib "RES") (part "0805 1KΩ (1001) 1%"))
    )
    (comp (ref "R122")
      (value "1KΩ (1001) ±1%")
      (footprint "0805_R")
      (description "贴片电阻")
      (libsource (lib "RES") (part "0805 1KΩ (1001) 1%"))
    )
    (comp (ref "R123")
      (value "1KΩ (1001) ±1%")
      (footprint "0805_R")
      (description "贴片电阻")
      (libsource (lib "RES") (part "0805 1KΩ (1001) 1%"))
    )
    (comp (ref "R124")
      (value "3.3KΩ (3301) ±1%")
      (footprint "0603_R")
      (description "贴片电阻")
      (libsource (lib "RES") (part "0603 3.3KΩ (3301) 1%"))
    )
    (comp (ref "R125")
      (value "3.3KΩ (3301) ±1%")
      (footprint "0603_R")
      (description "贴片电阻")
      (libsource (lib "RES") (part "0603 3.3KΩ (3301) 1%"))
    )
    (comp (ref "R126")
      (value "3.3KΩ (3301) ±1%")
      (footprint "0603_R")
      (description "贴片电阻")
      (libsource (lib "RES") (part "0603 3.3KΩ (3301) 1%"))
    )
    (comp (ref "R127")
      (value "3.3KΩ (3301) ±1%")
      (footprint "0603_R")
      (description "贴片电阻")
      (libsource (lib "RES") (part "0603 3.3KΩ (3301) 1%"))
    )
    (comp (ref "R128")
      (value "3.3KΩ (3301) ±1%")
      (footprint "0603_R")
      (description "贴片电阻")
      (libsource (lib "RES") (part "0603 3.3KΩ (3301) 1%"))
    )
    (comp (ref "R129")
      (value "3.3KΩ (3301) ±1%")
      (footprint "0603_R")
      (description "贴片电阻")
      (libsource (lib "RES") (part "0603 3.3KΩ (3301) 1%"))
    )
    (comp (ref "R130")
      (value "1KΩ (1001) ±1%")
      (footprint "0603_R")
      (description "贴片电阻")
      (libsource (lib "RES") (part "0603 1KΩ (1001) 1%"))
    )
    (comp (ref "R131")
      (value "1KΩ (1001) ±1%")
      (footprint "0603_R")
      (description "贴片电阻")
      (libsource (lib "RES") (part "0603 1KΩ (1001) 1%"))
    )
    (comp (ref "R132")
      (value "1KΩ (1001) ±1%")
      (footprint "0603_R")
      (description "贴片电阻")
      (libsource (lib "RES") (part "0603 1KΩ (1001) 1%"))
    )
    (comp (ref "R133")
      (value "1KΩ (1001) ±1%")
      (footprint "0603_R")
      (description "贴片电阻")
      (libsource (lib "RES") (part "0603 1KΩ (1001) 1%"))
    )
    (comp (ref "R134")
      (value "1KΩ (1001) ±1%")
      (footprint "0603_R")
      (description "贴片电阻")
      (libsource (lib "RES") (part "0603 1KΩ (1001) 1%"))
    )
    (comp (ref "R135")
      (value "1KΩ (1001) ±1%")
      (footprint "0603_R")
      (description "贴片电阻")
      (libsource (lib "RES") (part "0603 1KΩ (1001) 1%"))
    )
    (comp (ref "R136")
      (value "3.3KΩ (3301) ±1%")
      (footprint "0603_R")
      (description "贴片电阻")
      (libsource (lib "RES") (part "0603 3.3KΩ (3301) 1%"))
    )
    (comp (ref "R137")
      (value "3.3KΩ (3301) ±1%")
      (footprint "0603_R")
      (description "贴片电阻")
      (libsource (lib "RES") (part "0603 3.3KΩ (3301) 1%"))
    )
    (comp (ref "R138")
      (value "1KΩ (1001) ±1%")
      (footprint "0603_R")
      (description "贴片电阻")
      (libsource (lib "RES") (part "0603 1KΩ (1001) 1%"))
    )
    (comp (ref "R139")
      (value "1KΩ (1001) ±1%")
      (footprint "0603_R")
      (description "贴片电阻")
      (libsource (lib "RES") (part "0603 1KΩ (1001) 1%"))
    )
    (comp (ref "U8")
      (value "74HC165D")
      (footprint "SOIC-16_150mil")
      (description "74系列逻辑芯片")
      (libsource (lib "IC") (part "74HC165D_[C5613]"))
    )
    (comp (ref "U9")
      (value "74HC165D")
      (footprint "SOIC-16_150mil")
      (description "74系列逻辑芯片")
      (libsource (lib "IC") (part "74HC165D_[C5613]"))
    )
    (comp (ref "U10")
      (value "74HC165D")
      (footprint "SOIC-16_150mil")
      (description "74系列逻辑芯片")
      (libsource (lib "IC") (part "74HC165D_[C5613]"))
    )
    (comp (ref "U11")
      (value "MP1482DS")
      (footprint "SOIC-8_150mil")
      (description "电源芯片")
      (libsource (lib "IC") (part "MP1482DS_[C14867]"))
    )
    (comp (ref "U12")
      (value "EL357N(B)(TA)-G")
      (footprint "SOP-4_P2.54")
      (description "贴片光耦")
      (libsource (lib "IC") (part "EL357N(B)(TA)-G_[C6649]"))
    )
    (comp (ref "U13")
      (value "EL357N(B)(TA)-G")
      (footprint "SOP-4_P2.54")
      (description "贴片光耦")
      (libsource (lib "IC") (part "EL357N(B)(TA)-G_[C6649]"))
    )
    (comp (ref "U14")
      (value "EL357N(B)(TA)-G")
      (footprint "SOP-4_P2.54")
      (description "贴片光耦")
      (libsource (lib "IC") (part "EL357N(B)(TA)-G_[C6649]"))
    )
    (comp (ref "U15")
      (value "EL357N(B)(TA)-G")
      (footprint "SOP-4_P2.54")
      (description "贴片光耦")
      (libsource (lib "IC") (part "EL357N(B)(TA)-G_[C6649]"))
    )
    (comp (ref "U16")
      (value "EL357N(B)(TA)-G")
      (footprint "SOP-4_P2.54")
      (description "贴片光耦")
      (libsource (lib "IC") (part "EL357N(B)(TA)-G_[C6649]"))
    )
    (comp (ref "U17")
      (value "EL357N(B)(TA)-G")
      (footprint "SOP-4_P2.54")
      (description "贴片光耦")
      (libsource (lib "IC") (part "EL357N(B)(TA)-G_[C6649]"))
    )
    (comp (ref "U18")
      (value "EL357N(B)(TA)-G")
      (footprint "SOP-4_P2.54")
      (description "贴片光耦")
      (libsource (lib "IC") (part "EL357N(B)(TA)-G_[C6649]"))
    )
    (comp (ref "U19")
      (value "EL357N(B)(TA)-G")
      (footprint "SOP-4_P2.54")
      (description "贴片光耦")
      (libsource (lib "IC") (part "EL357N(B)(TA)-G_[C6649]"))
    )
    (comp (ref "U20")
      (value "EL357N(B)(TA)-G")
      (footprint "SOP-4_P2.54")
      (description "贴片光耦")
      (libsource (lib "IC") (part "EL357N(B)(TA)-G_[C6649]"))
    )
    (comp (ref "U21")
      (value "EL357N(B)(TA)-G")
      (footprint "SOP-4_P2.54")
      (description "贴片光耦")
      (libsource (lib "IC") (part "EL357N(B)(TA)-G_[C6649]"))
    )
    (comp (ref "U22")
      (value "EL357N(B)(TA)-G")
      (footprint "SOP-4_P2.54")
      (description "贴片光耦")
      (libsource (lib "IC") (part "EL357N(B)(TA)-G_[C6649]"))
    )
    (comp (ref "U23")
      (value "EL357N(B)(TA)-G")
      (footprint "SOP-4_P2.54")
      (description "贴片光耦")
      (libsource (lib "IC") (part "EL357N(B)(TA)-G_[C6649]"))
    )
    (comp (ref "U24")
      (value "EL357N(B)(TA)-G")
      (footprint "SOP-4_P2.54")
      (description "贴片光耦")
      (libsource (lib "IC") (part "EL357N(B)(TA)-G_[C6649]"))
    )
    (comp (ref "U25")
      (value "EL357N(B)(TA)-G")
      (footprint "SOP-4_P2.54")
      (description "贴片光耦")
      (libsource (lib "IC") (part "EL357N(B)(TA)-G_[C6649]"))
    )
    (comp (ref "U26")
      (value "EL357N(B)(TA)-G")
      (footprint "SOP-4_P2.54")
      (description "贴片光耦")
      (libsource (lib "IC") (part "EL357N(B)(TA)-G_[C6649]"))
    )
    (comp (ref "U27")
      (value "EL357N(B)(TA)-G")
      (footprint "SOP-4_P2.54")
      (description "贴片光耦")
      (libsource (lib "IC") (part "EL357N(B)(TA)-G_[C6649]"))
    )
    (comp (ref "U28")
      (value "EL357N(B)(TA)-G")
      (footprint "SOP-4_P2.54")
      (description "贴片光耦")
      (libsource (lib "IC") (part "EL357N(B)(TA)-G_[C6649]"))
    )
    (comp (ref "U29")
      (value "EL357N(B)(TA)-G")
      (footprint "SOP-4_P2.54")
      (description "贴片光耦")
      (libsource (lib "IC") (part "EL357N(B)(TA)-G_[C6649]"))
    )
    (comp (ref "U30")
      (value "EL357N(B)(TA)-G")
      (footprint "SOP-4_P2.54")
      (description "贴片光耦")
      (libsource (lib "IC") (part "EL357N(B)(TA)-G_[C6649]"))
    )
    (comp (ref "U31")
      (value "EL357N(B)(TA)-G")
      (footprint "SOP-4_P2.54")
      (description "贴片光耦")
      (libsource (lib "IC") (part "EL357N(B)(TA)-G_[C6649]"))
    )
    (comp (ref "U32")
      (value "EL357N(B)(TA)-G")
      (footprint "SOP-4_P2.54")
      (description "贴片光耦")
      (libsource (lib "IC") (part "EL357N(B)(TA)-G_[C6649]"))
    )
    (comp (ref "U33")
      (value "EL357N(B)(TA)-G")
      (footprint "SOP-4_P2.54")
      (description "贴片光耦")
      (libsource (lib "IC") (part "EL357N(B)(TA)-G_[C6649]"))
    )
    (comp (ref "U34")
      (value "EL357N(B)(TA)-G")
      (footprint "SOP-4_P2.54")
      (description "贴片光耦")
      (libsource (lib "IC") (part "EL357N(B)(TA)-G_[C6649]"))
    )
    (comp (ref "U35")
      (value "EL357N(B)(TA)-G")
      (footprint "SOP-4_P2.54")
      (description "贴片光耦")
      (libsource (lib "IC") (part "EL357N(B)(TA)-G_[C6649]"))
    )
    (comp (ref "U36")
      (value "74HC595D")
      (footprint "SOIC-16_150mil")
      (description "74系列逻辑芯片")
      (libsource (lib "IC") (part "74HC595D_[C5947]"))
    )
  )
  (nets
    (net (code "1") (name "+12") (class "Default")
      (node (ref "C44") (pin "2") (pinfunction "2_2") (pintype "passive"))
      (node (ref "D16") (pin "2") (pinfunction "K_2") (pintype "passive"))
      (node (ref "P23") (pin "2") (pinfunction "2_2") (pintype "passive"))
      (node (ref "P24") (pin "1") (pinfunction "1_1") (pintype "passive"))
      (node (ref "P25") (pin "1") (pinfunction "1_1") (pintype "passive"))
      (node (ref "P26") (pin "1") (pinfunction "1_1") (pintype "passive"))
      (node (ref "P27") (pin "1") (pinfunction "1_1") (pintype "passive"))
      (node (ref "P28") (pin "1") (pinfunction "1_1") (pintype "passive"))
      (node (ref "P29") (pin "1") (pinfunction "1_1") (pintype "passive"))
      (node (ref "P30") (pin "1") (pinfunction "1_1") (pintype "passive"))
      (node (ref "P31") (pin "1") (pinfunction "1_1") (pintype "passive"))
      (node (ref "R47") (pin "1") (pinfunction "1_1") (pintype "passive"))
      (node (ref "U11") (pin "2") (pinfunction "IN_2") (pintype "passive"))
    )
    (net (code "3") (name "/ALARM") (class "Default")
      (node (ref "P14") (pin "9") (pinfunction "9_9") (pintype "passive"))
      (node (ref "U36") (pin "14") (pinfunction "SER_14") (pintype "input"))
    )
    (net (code "4") (name "/ALARM0") (class "Default")
      (node (ref "C77") (pin "1") (pinfunction "1_1") (pintype "passive"))
      (node (ref "D49") (pin "A") (pinfunction "A_A") (pintype "passive"))
      (node (ref "R130") (pin "1") (pinfunction "1_1") (pintype "passive"))
      (node (ref "U36") (pin "15") (pinfunction "QA_15") (pintype "tri_state"))
    )
    (net (code "5") (name "/ALARM1") (class "Default")
      (node (ref "C78") (pin "1") (pinfunction "1_1") (pintype "passive"))
      (node (ref "D50") (pin "A") (pinfunction "A_A") (pintype "passive"))
      (node (ref "R131") (pin "1") (pinfunction "1_1") (pintype "passive"))
      (node (ref "U36") (pin "1") (pinfunction "QB_1") (pintype "tri_state"))
    )
    (net (code "6") (name "/ALARM2") (class "Default")
      (node (ref "C79") (pin "1") (pinfunction "1_1") (pintype "passive"))
      (node (ref "D51") (pin "A") (pinfunction "A_A") (pintype "passive"))
      (node (ref "R132") (pin "1") (pinfunction "1_1") (pintype "passive"))
      (node (ref "U36") (pin "2") (pinfunction "QC_2") (pintype "tri_state"))
    )
    (net (code "7") (name "/ALARM3") (class "Default")
      (node (ref "C80") (pin "1") (pinfunction "1_1") (pintype "passive"))
      (node (ref "D52") (pin "A") (pinfunction "A_A") (pintype "passive"))
      (node (ref "R133") (pin "1") (pinfunction "1_1") (pintype "passive"))
      (node (ref "U36") (pin "3") (pinfunction "QD_3") (pintype "tri_state"))
    )
    (net (code "8") (name "/ALARM4") (class "Default")
      (node (ref "C81") (pin "1") (pinfunction "1_1") (pintype "passive"))
      (node (ref "D53") (pin "A") (pinfunction "A_A") (pintype "passive"))
      (node (ref "R134") (pin "1") (pinfunction "1_1") (pintype "passive"))
      (node (ref "U36") (pin "4") (pinfunction "QE_4") (pintype "tri_state"))
    )
    (net (code "9") (name "/ALARM5") (class "Default")
      (node (ref "C82") (pin "1") (pinfunction "1_1") (pintype "passive"))
      (node (ref "D54") (pin "A") (pinfunction "A_A") (pintype "passive"))
      (node (ref "R135") (pin "1") (pinfunction "1_1") (pintype "passive"))
      (node (ref "U36") (pin "5") (pinfunction "QF_5") (pintype "tri_state"))
    )
    (net (code "10") (name "/ALARM6") (class "Default")
      (node (ref "C84") (pin "1") (pinfunction "1_1") (pintype "passive"))
      (node (ref "D57") (pin "A") (pinfunction "A_A") (pintype "passive"))
      (node (ref "R138") (pin "1") (pinfunction "1_1") (pintype "passive"))
      (node (ref "U36") (pin "6") (pinfunction "QG_6") (pintype "tri_state"))
    )
    (net (code "11") (name "/ALARM7") (class "Default")
      (node (ref "C85") (pin "1") (pinfunction "1_1") (pintype "passive"))
      (node (ref "D58") (pin "A") (pinfunction "A_A") (pintype "passive"))
      (node (ref "R139") (pin "1") (pinfunction "1_1") (pintype "passive"))
      (node (ref "U36") (pin "7") (pinfunction "QH_7") (pintype "tri_state"))
    )
    (net (code "12") (name "/ALARM_LAST") (class "Default")
      (node (ref "P13") (pin "9") (pinfunction "9_9") (pintype "passive"))
      (node (ref "U36") (pin "9") (pinfunction "QH'_9") (pintype "output"))
    )
    (net (code "13") (name "/CLK") (class "Default")
      (node (ref "P13") (pin "1") (pinfunction "1_1") (pintype "passive"))
      (node (ref "P14") (pin "1") (pinfunction "1_1") (pintype "passive"))
      (node (ref "U10") (pin "2") (pinfunction "CLK_2") (pintype "input"))
      (node (ref "U36") (pin "11") (pinfunction "SRCLK_11") (pintype "input"))
      (node (ref "U8") (pin "2") (pinfunction "CLK_2") (pintype "input"))
      (node (ref "U9") (pin "2") (pinfunction "CLK_2") (pintype "input"))
    )
    (net (code "14") (name "/LE") (class "Default")
      (node (ref "P13") (pin "5") (pinfunction "5_5") (pintype "passive"))
      (node (ref "P14") (pin "5") (pinfunction "5_5") (pintype "passive"))
      (node (ref "U36") (pin "12") (pinfunction "RCLK_12") (pintype "input"))
    )
    (net (code "15") (name "/PE") (class "Default")
      (node (ref "P13") (pin "3") (pinfunction "3_3") (pintype "passive"))
      (node (ref "P14") (pin "3") (pinfunction "3_3") (pintype "passive"))
      (node (ref "U10") (pin "1") (pinfunction "S/L_1") (pintype "input"))
      (node (ref "U8") (pin "1") (pinfunction "S/L_1") (pintype "input"))
      (node (ref "U9") (pin "1") (pinfunction "S/L_1") (pintype "input"))
    )
    (net (code "16") (name "/S0") (class "Default")
      (node (ref "P15") (pin "3") (pinfunction "3_3") (pintype "passive"))
      (node (ref "R68") (pin "1") (pinfunction "1_1") (pintype "passive"))
    )
    (net (code "17") (name "/S1") (class "Default")
      (node (ref "P15") (pin "2") (pinfunction "2_2") (pintype "passive"))
      (node (ref "R69") (pin "1") (pinfunction "1_1") (pintype "passive"))
    )
    (net (code "18") (name "/S2") (class "Default")
      (node (ref "P15") (pin "1") (pinfunction "1_1") (pintype "passive"))
      (node (ref "R70") (pin "1") (pinfunction "1_1") (pintype "passive"))
    )
    (net (code "19") (name "/S3") (class "Default")
      (node (ref "P16") (pin "3") (pinfunction "3_3") (pintype "passive"))
      (node (ref "R71") (pin "1") (pinfunction "1_1") (pintype "passive"))
    )
    (net (code "20") (name "/S4") (class "Default")
      (node (ref "P16") (pin "2") (pinfunction "2_2") (pintype "passive"))
      (node (ref "R72") (pin "1") (pinfunction "1_1") (pintype "passive"))
    )
    (net (code "21") (name "/S5") (class "Default")
      (node (ref "P16") (pin "1") (pinfunction "1_1") (pintype "passive"))
      (node (ref "R73") (pin "1") (pinfunction "1_1") (pintype "passive"))
    )
    (net (code "22") (name "/S6") (class "Default")
      (node (ref "P17") (pin "3") (pinfunction "3_3") (pintype "passive"))
      (node (ref "R74") (pin "1") (pinfunction "1_1") (pintype "passive"))
    )
    (net (code "23") (name "/S7") (class "Default")
      (node (ref "P17") (pin "2") (pinfunction "2_2") (pintype "passive"))
      (node (ref "R75") (pin "1") (pinfunction "1_1") (pintype "passive"))
    )
    (net (code "24") (name "/S8") (class "Default")
      (node (ref "P17") (pin "1") (pinfunction "1_1") (pintype "passive"))
      (node (ref "R92") (pin "1") (pinfunction "1_1") (pintype "passive"))
    )
    (net (code "25") (name "/S9") (class "Default")
      (node (ref "P18") (pin "3") (pinfunction "3_3") (pintype "passive"))
      (node (ref "R93") (pin "1") (pinfunction "1_1") (pintype "passive"))
    )
    (net (code "26") (name "/S10") (class "Default")
      (node (ref "P18") (pin "2") (pinfunction "2_2") (pintype "passive"))
      (node (ref "R94") (pin "1") (pinfunction "1_1") (pintype "passive"))
    )
    (net (code "27") (name "/S11") (class "Default")
      (node (ref "P18") (pin "1") (pinfunction "1_1") (pintype "passive"))
      (node (ref "R95") (pin "1") (pinfunction "1_1") (pintype "passive"))
    )
    (net (code "28") (name "/S12") (class "Default")
      (node (ref "P19") (pin "3") (pinfunction "3_3") (pintype "passive"))
      (node (ref "R96") (pin "1") (pinfunction "1_1") (pintype "passive"))
    )
    (net (code "29") (name "/S13") (class "Default")
      (node (ref "P19") (pin "2") (pinfunction "2_2") (pintype "passive"))
      (node (ref "R97") (pin "1") (pinfunction "1_1") (pintype "passive"))
    )
    (net (code "30") (name "/S14") (class "Default")
      (node (ref "P19") (pin "1") (pinfunction "1_1") (pintype "passive"))
      (node (ref "R98") (pin "1") (pinfunction "1_1") (pintype "passive"))
    )
    (net (code "31") (name "/S15") (class "Default")
      (node (ref "P20") (pin "3") (pinfunction "3_3") (pintype "passive"))
      (node (ref "R99") (pin "1") (pinfunction "1_1") (pintype "passive"))
    )
    (net (code "32") (name "/S16") (class "Default")
      (node (ref "P20") (pin "2") (pinfunction "2_2") (pintype "passive"))
      (node (ref "R116") (pin "1") (pinfunction "1_1") (pintype "passive"))
    )
    (net (code "33") (name "/S17") (class "Default")
      (node (ref "P20") (pin "1") (pinfunction "1_1") (pintype "passive"))
      (node (ref "R117") (pin "1") (pinfunction "1_1") (pintype "passive"))
    )
    (net (code "34") (name "/S18") (class "Default")
      (node (ref "P21") (pin "3") (pinfunction "3_3") (pintype "passive"))
      (node (ref "R118") (pin "1") (pinfunction "1_1") (pintype "passive"))
    )
    (net (code "35") (name "/S19") (class "Default")
      (node (ref "P21") (pin "2") (pinfunction "2_2") (pintype "passive"))
      (node (ref "R119") (pin "1") (pinfunction "1_1") (pintype "passive"))
    )
    (net (code "36") (name "/S20") (class "Default")
      (node (ref "P21") (pin "1") (pinfunction "1_1") (pintype "passive"))
      (node (ref "R120") (pin "1") (pinfunction "1_1") (pintype "passive"))
    )
    (net (code "37") (name "/S21") (class "Default")
      (node (ref "P22") (pin "3") (pinfunction "3_3") (pintype "passive"))
      (node (ref "R121") (pin "1") (pinfunction "1_1") (pintype "passive"))
    )
    (net (code "38") (name "/S22") (class "Default")
      (node (ref "P22") (pin "2") (pinfunction "2_2") (pintype "passive"))
      (node (ref "R122") (pin "1") (pinfunction "1_1") (pintype "passive"))
    )
    (net (code "39") (name "/S23") (class "Default")
      (node (ref "P22") (pin "1") (pinfunction "1_1") (pintype "passive"))
      (node (ref "R123") (pin "1") (pinfunction "1_1") (pintype "passive"))
    )
    (net (code "40") (name "/SIN0") (class "Default")
      (node (ref "C53") (pin "1") (pinfunction "1_1") (pintype "passive"))
      (node (ref "R52") (pin "1") (pinfunction "1_1") (pintype "passive"))
      (node (ref "R60") (pin "2") (pinfunction "2_2") (pintype "passive"))
      (node (ref "U12") (pin "4") (pinfunction "C_4") (pintype "passive"))
      (node (ref "U8") (pin "11") (pinfunction "A_11") (pintype "input"))
    )
    (net (code "41") (name "/SIN1") (class "Default")
      (node (ref "C54") (pin "1") (pinfunction "1_1") (pintype "passive"))
      (node (ref "R53") (pin "1") (pinfunction "1_1") (pintype "passive"))
      (node (ref "R61") (pin "2") (pinfunction "2_2") (pintype "passive"))
      (node (ref "U13") (pin "4") (pinfunction "C_4") (pintype "passive"))
      (node (ref "U8") (pin "12") (pinfunction "B_12") (pintype "input"))
    )
    (net (code "42") (name "/SIN2") (class "Default")
      (node (ref "C55") (pin "1") (pinfunction "1_1") (pintype "passive"))
      (node (ref "R54") (pin "1") (pinfunction "1_1") (pintype "passive"))
      (node (ref "R62") (pin "2") (pinfunction "2_2") (pintype "passive"))
      (node (ref "U14") (pin "4") (pinfunction "C_4") (pintype "passive"))
      (node (ref "U8") (pin "13") (pinfunction "C_13") (pintype "input"))
    )
    (net (code "43") (name "/SIN3") (class "Default")
      (node (ref "C56") (pin "1") (pinfunction "1_1") (pintype "passive"))
      (node (ref "R55") (pin "1") (pinfunction "1_1") (pintype "passive"))
      (node (ref "R63") (pin "2") (pinfunction "2_2") (pintype "passive"))
      (node (ref "U15") (pin "4") (pinfunction "C_4") (pintype "passive"))
      (node (ref "U8") (pin "14") (pinfunction "D_14") (pintype "input"))
    )
    (net (code "44") (name "/SIN4") (class "Default")
      (node (ref "C57") (pin "1") (pinfunction "1_1") (pintype "passive"))
      (node (ref "R56") (pin "1") (pinfunction "1_1") (pintype "passive"))
      (node (ref "R64") (pin "2") (pinfunction "2_2") (pintype "passive"))
      (node (ref "U16") (pin "4") (pinfunction "C_4") (pintype "passive"))
      (node (ref "U8") (pin "3") (pinfunction "E_3") (pintype "input"))
    )
    (net (code "45") (name "/SIN5") (class "Default")
      (node (ref "C58") (pin "1") (pinfunction "1_1") (pintype "passive"))
      (node (ref "R57") (pin "1") (pinfunction "1_1") (pintype "passive"))
      (node (ref "R65") (pin "2") (pinfunction "2_2") (pintype "passive"))
      (node (ref "U17") (pin "4") (pinfunction "C_4") (pintype "passive"))
      (node (ref "U8") (pin "4") (pinfunction "F_4") (pintype "input"))
    )
    (net (code "46") (name "/SIN6") (class "Default")
      (node (ref "C59") (pin "1") (pinfunction "1_1") (pintype "passive"))
      (node (ref "R58") (pin "1") (pinfunction "1_1") (pintype "passive"))
      (node (ref "R66") (pin "2") (pinfunction "2_2") (pintype "passive"))
      (node (ref "U18") (pin "4") (pinfunction "C_4") (pintype "passive"))
      (node (ref "U8") (pin "5") (pinfunction "G_5") (pintype "input"))
    )
    (net (code "47") (name "/SIN7") (class "Default")
      (node (ref "C60") (pin "1") (pinfunction "1_1") (pintype "passive"))
      (node (ref "R59") (pin "1") (pinfunction "1_1") (pintype "passive"))
      (node (ref "R67") (pin "2") (pinfunction "2_2") (pintype "passive"))
      (node (ref "U19") (pin "4") (pinfunction "C_4") (pintype "passive"))
      (node (ref "U8") (pin "6") (pinfunction "H_6") (pintype "input"))
    )
    (net (code "48") (name "/SIN8") (class "Default")
      (node (ref "C61") (pin "1") (pinfunction "1_1") (pintype "passive"))
      (node (ref "R76") (pin "1") (pinfunction "1_1") (pintype "passive"))
      (node (ref "R84") (pin "2") (pinfunction "2_2") (pintype "passive"))
      (node (ref "U20") (pin "4") (pinfunction "C_4") (pintype "passive"))
      (node (ref "U9") (pin "11") (pinfunction "A_11") (pintype "input"))
    )
    (net (code "49") (name "/SIN9") (class "Default")
      (node (ref "C62") (pin "1") (pinfunction "1_1") (pintype "passive"))
      (node (ref "R77") (pin "1") (pinfunction "1_1") (pintype "passive"))
      (node (ref "R85") (pin "2") (pinfunction "2_2") (pintype "passive"))
      (node (ref "U21") (pin "4") (pinfunction "C_4") (pintype "passive"))
      (node (ref "U9") (pin "12") (pinfunction "B_12") (pintype "input"))
    )
    (net (code "50") (name "/SIN10") (class "Default")
      (node (ref "C63") (pin "1") (pinfunction "1_1") (pintype "passive"))
      (node (ref "R78") (pin "1") (pinfunction "1_1") (pintype "passive"))
      (node (ref "R86") (pin "2") (pinfunction "2_2") (pintype "passive"))
      (node (ref "U22") (pin "4") (pinfunction "C_4") (pintype "passive"))
      (node (ref "U9") (pin "13") (pinfunction "C_13") (pintype "input"))
    )
    (net (code "51") (name "/SIN11") (class "Default")
      (node (ref "C64") (pin "1") (pinfunction "1_1") (pintype "passive"))
      (node (ref "R79") (pin "1") (pinfunction "1_1") (pintype "passive"))
      (node (ref "R87") (pin "2") (pinfunction "2_2") (pintype "passive"))
      (node (ref "U23") (pin "4") (pinfunction "C_4") (pintype "passive"))
      (node (ref "U9") (pin "14") (pinfunction "D_14") (pintype "input"))
    )
    (net (code "52") (name "/SIN12") (class "Default")
      (node (ref "C65") (pin "1") (pinfunction "1_1") (pintype "passive"))
      (node (ref "R80") (pin "1") (pinfunction "1_1") (pintype "passive"))
      (node (ref "R88") (pin "2") (pinfunction "2_2") (pintype "passive"))
      (node (ref "U24") (pin "4") (pinfunction "C_4") (pintype "passive"))
      (node (ref "U9") (pin "3") (pinfunction "E_3") (pintype "input"))
    )
    (net (code "53") (name "/SIN13") (class "Default")
      (node (ref "C66") (pin "1") (pinfunction "1_1") (pintype "passive"))
      (node (ref "R81") (pin "1") (pinfunction "1_1") (pintype "passive"))
      (node (ref "R89") (pin "2") (pinfunction "2_2") (pintype "passive"))
      (node (ref "U25") (pin "4") (pinfunction "C_4") (pintype "passive"))
      (node (ref "U9") (pin "4") (pinfunction "F_4") (pintype "input"))
    )
    (net (code "54") (name "/SIN14") (class "Default")
      (node (ref "C67") (pin "1") (pinfunction "1_1") (pintype "passive"))
      (node (ref "R82") (pin "1") (pinfunction "1_1") (pintype "passive"))
      (node (ref "R90") (pin "2") (pinfunction "2_2") (pintype "passive"))
      (node (ref "U26") (pin "4") (pinfunction "C_4") (pintype "passive"))
      (node (ref "U9") (pin "5") (pinfunction "G_5") (pintype "input"))
    )
    (net (code "55") (name "/SIN15") (class "Default")
      (node (ref "C68") (pin "1") (pinfunction "1_1") (pintype "passive"))
      (node (ref "R83") (pin "1") (pinfunction "1_1") (pintype "passive"))
      (node (ref "R91") (pin "2") (pinfunction "2_2") (pintype "passive"))
      (node (ref "U27") (pin "4") (pinfunction "C_4") (pintype "passive"))
      (node (ref "U9") (pin "6") (pinfunction "H_6") (pintype "input"))
    )
    (net (code "56") (name "/SIN16") (class "Default")
      (node (ref "C69") (pin "1") (pinfunction "1_1") (pintype "passive"))
      (node (ref "R100") (pin "1") (pinfunction "1_1") (pintype "passive"))
      (node (ref "R108") (pin "2") (pinfunction "2_2") (pintype "passive"))
      (node (ref "U10") (pin "11") (pinfunction "A_11") (pintype "input"))
      (node (ref "U28") (pin "4") (pinfunction "C_4") (pintype "passive"))
    )
    (net (code "57") (name "/SIN17") (class "Default")
      (node (ref "C70") (pin "1") (pinfunction "1_1") (pintype "passive"))
      (node (ref "R101") (pin "1") (pinfunction "1_1") (pintype "passive"))
      (node (ref "R109") (pin "2") (pinfunction "2_2") (pintype "passive"))
      (node (ref "U10") (pin "12") (pinfunction "B_12") (pintype "input"))
      (node (ref "U29") (pin "4") (pinfunction "C_4") (pintype "passive"))
    )
    (net (code "58") (name "/SIN18") (class "Default")
      (node (ref "C71") (pin "1") (pinfunction "1_1") (pintype "passive"))
      (node (ref "R102") (pin "1") (pinfunction "1_1") (pintype "passive"))
      (node (ref "R110") (pin "2") (pinfunction "2_2") (pintype "passive"))
      (node (ref "U10") (pin "13") (pinfunction "C_13") (pintype "input"))
      (node (ref "U30") (pin "4") (pinfunction "C_4") (pintype "passive"))
    )
    (net (code "59") (name "/SIN19") (class "Default")
      (node (ref "C72") (pin "1") (pinfunction "1_1") (pintype "passive"))
      (node (ref "R103") (pin "1") (pinfunction "1_1") (pintype "passive"))
      (node (ref "R111") (pin "2") (pinfunction "2_2") (pintype "passive"))
      (node (ref "U10") (pin "14") (pinfunction "D_14") (pintype "input"))
      (node (ref "U31") (pin "4") (pinfunction "C_4") (pintype "passive"))
    )
    (net (code "60") (name "/SIN20") (class "Default")
      (node (ref "C73") (pin "1") (pinfunction "1_1") (pintype "passive"))
      (node (ref "R104") (pin "1") (pinfunction "1_1") (pintype "passive"))
      (node (ref "R112") (pin "2") (pinfunction "2_2") (pintype "passive"))
      (node (ref "U10") (pin "3") (pinfunction "E_3") (pintype "input"))
      (node (ref "U32") (pin "4") (pinfunction "C_4") (pintype "passive"))
    )
    (net (code "61") (name "/SIN21") (class "Default")
      (node (ref "C74") (pin "1") (pinfunction "1_1") (pintype "passive"))
      (node (ref "R105") (pin "1") (pinfunction "1_1") (pintype "passive"))
      (node (ref "R113") (pin "2") (pinfunction "2_2") (pintype "passive"))
      (node (ref "U10") (pin "4") (pinfunction "F_4") (pintype "input"))
      (node (ref "U33") (pin "4") (pinfunction "C_4") (pintype "passive"))
    )
    (net (code "62") (name "/SIN22") (class "Default")
      (node (ref "C75") (pin "1") (pinfunction "1_1") (pintype "passive"))
      (node (ref "R106") (pin "1") (pinfunction "1_1") (pintype "passive"))
      (node (ref "R114") (pin "2") (pinfunction "2_2") (pintype "passive"))
      (node (ref "U10") (pin "5") (pinfunction "G_5") (pintype "input"))
      (node (ref "U34") (pin "4") (pinfunction "C_4") (pintype "passive"))
    )
    (net (code "63") (name "/SIN23") (class "Default")
      (node (ref "C76") (pin "1") (pinfunction "1_1") (pintype "passive"))
      (node (ref "R107") (pin "1") (pinfunction "1_1") (pintype "passive"))
      (node (ref "R115") (pin "2") (pinfunction "2_2") (pintype "passive"))
      (node (ref "U10") (pin "6") (pinfunction "H_6") (pintype "input"))
      (node (ref "U35") (pin "4") (pinfunction "C_4") (pintype "passive"))
    )
    (net (code "64") (name "/SMOKE_IN") (class "Default")
      (node (ref "P14") (pin "7") (pinfunction "7_7") (pintype "passive"))
      (node (ref "U10") (pin "9") (pinfunction "QH_9") (pintype "output"))
    )
    (net (code "65") (name "/SMOKE_PREV") (class "Default")
      (node (ref "P13") (pin "7") (pinfunction "7_7") (pintype "passive"))
      (node (ref "U8") (pin "10") (pinfunction "SI_10") (pintype "input"))
    )
    (net (code "66") (name "5V") (class "Default")
      (node (ref "C45") (pin "1") (pinfunction "1_1") (pintype "passive"))
      (node (ref "C46") (pin "1") (pinfunction "1_1") (pintype "passive"))
      (node (ref "C47") (pin "1") (pinfunction "1_1") (pintype "passive"))
      (node (ref "C51") (pin "1") (pinfunction "1_1") (pintype "passive"))
      (node (ref "C52") (pin "1") (pinfunction "1_1") (pintype "passive"))
      (node (ref "C83") (pin "1") (pinfunction "1_1") (pintype "passive"))
      (node (ref "D17") (pin "A") (pinfunction "A_A") (pintype "passive"))
      (node (ref "D19") (pin "A") (pinfunction "A_A") (pintype "passive"))
      (node (ref "D20") (pin "A") (pinfunction "A_A") (pintype "passive"))
      (node (ref "D21") (pin "A") (pinfunction "A_A") (pintype "passive"))
      (node (ref "D22") (pin "A") (pinfunction "A_A") (pintype "passive"))
      (node (ref "D23") (pin "A") (pinfunction "A_A") (pintype "passive"))
      (node (ref "D24") (pin "A") (pinfunction "A_A") (pintype "passive"))
      (node (ref "D25") (pin "A") (pinfunction "A_A") (pintype "passive"))
      (node (ref "D26") (pin "A") (pinfunction "A_A") (pintype "passive"))
      (node (ref "D27") (pin "A") (pinfunction "A_A") (pintype "passive"))
      (node (ref "D28") (pin "A") (pinfunction "A_A") (pintype "passive"))
      (node (ref "D29") (pin "A") (pinfunction "A_A") (pintype "passive"))
      (node (ref "D30") (pin "A") (pinfunction "A_A") (pintype "passive"))
      (node (ref "D31") (pin "A") (pinfunction "A_A") (pintype "passive"))
      (node (ref "D32") (pin "A") (pinfunction "A_A") (pintype "passive"))
      (node (ref "D33") (pin "A") (pinfunction "A_A") (pintype "passive"))
      (node (ref "D34") (pin "A") (pinfunction "A_A") (pintype "passive"))
      (node (ref "D35") (pin "A") (pinfunction "A_A") (pintype "passive"))
      (node (ref "D36") (pin "A") (pinfunction "A_A") (pintype "passive"))
      (node (ref "D37") (pin "A") (pinfunction "A_A") (pintype "passive"))
      (node (ref "D38") (pin "A") (pinfunction "A_A") (pintype "passive"))
      (node (ref "D39") (pin "A") (pinfunction "A_A") (pintype "passive"))
      (node (ref "D40") (pin "A") (pinfunction "A_A") (pintype "passive"))
      (node (ref "D41") (pin "A") (pinfunction "A_A") (pintype "passive"))
      (node (ref "D42") (pin "A") (pinfunction "A_A") (pintype "passive"))
      (node (ref "D43") (pin "2") (pinfunction "K_2") (pintype "passive"))
      (node (ref "D44") (pin "2") (pinfunction "K_2") (pintype "passive"))
      (node (ref "D45") (pin "2") (pinfunction "K_2") (pintype "passive"))
      (node (ref "D46") (pin "2") (pinfunction "K_2") (pintype "passive"))
      (node (ref "D47") (pin "2") (pinfunction "K_2") (pintype "passive"))
      (node (ref "D48") (pin "2") (pinfunction "K_2") (pintype "passive"))
      (node (ref "D55") (pin "2") (pinfunction "K_2") (pintype "passive"))
      (node (ref "D56") (pin "2") (pinfunction "K_2") (pintype "passive"))
      (node (ref "K10") (pin "4") (pinfunction "4_4") (pintype "passive"))
      (node (ref "K3") (pin "4") (pinfunction "4_4") (pintype "passive"))
      (node (ref "K4") (pin "4") (pinfunction "4_4") (pintype "passive"))
      (node (ref "K5") (pin "4") (pinfunction "4_4") (pintype "passive"))
      (node (ref "K6") (pin "4") (pinfunction "4_4") (pintype "passive"))
      (node (ref "K7") (pin "4") (pinfunction "4_4") (pintype "passive"))
      (node (ref "K8") (pin "4") (pinfunction "4_4") (pintype "passive"))
      (node (ref "K9") (pin "4") (pinfunction "4_4") (pintype "passive"))
      (node (ref "L3") (pin "2") (pinfunction "2_2") (pintype "passive"))
      (node (ref "R100") (pin "2") (pinfunction "2_2") (pintype "passive"))
      (node (ref "R101") (pin "2") (pinfunction "2_2") (pintype "passive"))
      (node (ref "R102") (pin "2") (pinfunction "2_2") (pintype "passive"))
      (node (ref "R103") (pin "2") (pinfunction "2_2") (pintype "passive"))
      (node (ref "R104") (pin "2") (pinfunction "2_2") (pintype "passive"))
      (node (ref "R105") (pin "2") (pinfunction "2_2") (pintype "passive"))
      (node (ref "R106") (pin "2") (pinfunction "2_2") (pintype "passive"))
      (node (ref "R107") (pin "2") (pinfunction "2_2") (pintype "passive"))
      (node (ref "R50") (pin "2") (pinfunction "2_2") (pintype "passive"))
      (node (ref "R52") (pin "2") (pinfunction "2_2") (pintype "passive"))
      (node (ref "R53") (pin "2") (pinfunction "2_2") (pintype "passive"))
      (node (ref "R54") (pin "2") (pinfunction "2_2") (pintype "passive"))
      (node (ref "R55") (pin "2") (pinfunction "2_2") (pintype "passive"))
      (node (ref "R56") (pin "2") (pinfunction "2_2") (pintype "passive"))
      (node (ref "R57") (pin "2") (pinfunction "2_2") (pintype "passive"))
      (node (ref "R58") (pin "2") (pinfunction "2_2") (pintype "passive"))
      (node (ref "R59") (pin "2") (pinfunction "2_2") (pintype "passive"))
      (node (ref "R76") (pin "2") (pinfunction "2_2") (pintype "passive"))
      (node (ref "R77") (pin "2") (pinfunction "2_2") (pintype "passive"))
      (node (ref "R78") (pin "2") (pinfunction "2_2") (pintype "passive"))
      (node (ref "R79") (pin "2") (pinfunction "2_2") (pintype "passive"))
      (node (ref "R80") (pin "2") (pinfunction "2_2") (pintype "passive"))
      (node (ref "R81") (pin "2") (pinfunction "2_2") (pintype "passive"))
      (node (ref "R82") (pin "2") (pinfunction "2_2") (pintype "passive"))
      (node (ref "R83") (pin "2") (pinfunction "2_2") (pintype "passive"))
      (node (ref "U10") (pin "16") (pinfunction "VCC_16") (pintype "power_in"))
      (node (ref "U36") (pin "10") (pinfunction "~{SRCLR}_10") (pintype "input"))
      (node (ref "U36") (pin "16") (pinfunction "VCC_16") (pintype "power_in"))
      (node (ref "U8") (pin "16") (pinfunction "VCC_16") (pintype "power_in"))
      (node (ref "U9") (pin "16") (pinfunction "VCC_16") (pintype "power_in"))
    )
    (net (code "67") (name "GND") (class "Default")
      (node (ref "C44") (pin "1") (pinfunction "1_1") (pintype "passive"))
      (node (ref "C45") (pin "2") (pinfunction "2_2") (pintype "passive"))
      (node (ref "C46") (pin "2") (pinfunction "2_2") (pintype "passive"))
      (node (ref "C47") (pin "2") (pinfunction "2_2") (pintype "passive"))
      (node (ref "C48") (pin "1") (pinfunction "1_1") (pintype "passive"))
      (node (ref "C51") (pin "2") (pinfunction "2_2") (pintype "passive"))
      (node (ref "C52") (pin "2") (pinfunction "2_2") (pintype "passive"))
      (node (ref "C53") (pin "2") (pinfunction "2_2") (pintype "passive"))
      (node (ref "C54") (pin "2") (pinfunction "2_2") (pintype "passive"))
      (node (ref "C55") (pin "2") (pinfunction "2_2") (pintype "passive"))
      (node (ref "C56") (pin "2") (pinfunction "2_2") (pintype "passive"))
      (node (ref "C57") (pin "2") (pinfunction "2_2") (pintype "passive"))
      (node (ref "C58") (pin "2") (pinfunction "2_2") (pintype "passive"))
      (node (ref "C59") (pin "2") (pinfunction "2_2") (pintype "passive"))
      (node (ref "C60") (pin "2") (pinfunction "2_2") (pintype "passive"))
      (node (ref "C61") (pin "2") (pinfunction "2_2") (pintype "passive"))
      (node (ref "C62") (pin "2") (pinfunction "2_2") (pintype "passive"))
      (node (ref "C63") (pin "2") (pinfunction "2_2") (pintype "passive"))
      (node (ref "C64") (pin "2") (pinfunction "2_2") (pintype "passive"))
      (node (ref "C65") (pin "2") (pinfunction "2_2") (pintype "passive"))
      (node (ref "C66") (pin "2") (pinfunction "2_2") (pintype "passive"))
      (node (ref "C67") (pin "2") (pinfunction "2_2") (pintype "passive"))
      (node (ref "C68") (pin "2") (pinfunction "2_2") (pintype "passive"))
      (node (ref "C69") (pin "2") (pinfunction "2_2") (pintype "passive"))
      (node (ref "C70") (pin "2") (pinfunction "2_2") (pintype "passive"))
      (node (ref "C71") (pin "2") (pinfunction "2_2") (pintype "passive"))
      (node (ref "C72") (pin "2") (pinfunction "2_2") (pintype "passive"))
      (node (ref "C73") (pin "2") (pinfunction "2_2") (pintype "passive"))
      (node (ref "C74") (pin "2") (pinfunction "2_2") (pintype "passive"))
      (node (ref "C75") (pin "2") (pinfunction "2_2") (pintype "passive"))
      (node (ref "C76") (pin "2") (pinfunction "2_2") (pintype "passive"))
      (node (ref "C77") (pin "2") (pinfunction "2_2") (pintype "passive"))
      (node (ref "C78") (pin "2") (pinfunction "2_2") (pintype "passive"))
      (node (ref "C79") (pin "2") (pinfunction "2_2") (pintype "passive"))
      (node (ref "C80") (pin "2") (pinfunction "2_2") (pintype "passive"))
      (node (ref "C81") (pin "2") (pinfunction "2_2") (pintype "passive"))
      (node (ref "C82") (pin "2") (pinfunction "2_2") (pintype "passive"))
      (node (ref "C83") (pin "2") (pinfunction "2_2") (pintype "passive"))
      (node (ref "C84") (pin "2") (pinfunction "2_2") (pintype "passive"))
      (node (ref "C85") (pin "2") (pinfunction "2_2") (pintype "passive"))
      (node (ref "D18") (pin "1") (pinfunction "A_1") (pintype "passive"))
      (node (ref "K10") (pin "2") (pinfunction "2_2") (pintype "passive"))
      (node (ref "K3") (pin "2") (pinfunction "2_2") (pintype "passive"))
      (node (ref "K4") (pin "2") (pinfunction "2_2") (pintype "passive"))
      (node (ref "K5") (pin "2") (pinfunction "2_2") (pintype "passive"))
      (node (ref "K6") (pin "2") (pinfunction "2_2") (pintype "passive"))
      (node (ref "K7") (pin "2") (pinfunction "2_2") (pintype "passive"))
      (node (ref "K8") (pin "2") (pinfunction "2_2") (pintype "passive"))
      (node (ref "K9") (pin "2") (pinfunction "2_2") (pintype "passive"))
      (node (ref "P12") (pin "2") (pinfunction "2_2") (pintype "passive"))
      (node (ref "P13") (pin "10") (pinfunction "10_10") (pintype "passive"))
      (node (ref "P13") (pin "2") (pinfunction "2_2") (pintype "passive"))
      (node (ref "P13") (pin "4") (pinfunction "4_4") (pintype "passive"))
      (node (ref "P13") (pin "6") (pinfunction "6_6") (pintype "passive"))
      (node (ref "P13") (pin "8") (pinfunction "8_8") (pintype "passive"))
      (node (ref "P14") (pin "10") (pinfunction "10_10") (pintype "passive"))
      (node (ref "P14") (pin "2") (pinfunction "2_2") (pintype "passive"))
      (node (ref "P14") (pin "4") (pinfunction "4_4") (pintype "passive"))
      (node (ref "P14") (pin "6") (pinfunction "6_6") (pintype "passive"))
      (node (ref "P14") (pin "8") (pinfunction "8_8") (pintype "passive"))
      (node (ref "P23") (pin "1") (pinfunction "1_1") (pintype "passive"))
      (node (ref "Q13") (pin "2") (pinfunction "E_2") (pintype "passive"))
      (node (ref "Q14") (pin "2") (pinfunction "E_2") (pintype "passive"))
      (node (ref "Q15") (pin "2") (pinfunction "E_2") (pintype "passive"))
      (node (ref "Q16") (pin "2") (pinfunction "E_2") (pintype "passive"))
      (node (ref "Q17") (pin "2") (pinfunction "E_2") (pintype "passive"))
      (node (ref "Q18") (pin "2") (pinfunction "E_2") (pintype "passive"))
      (node (ref "Q19") (pin "2") (pinfunction "E_2") (pintype "passive"))
      (node (ref "Q20") (pin "2") (pinfunction "E_2") (pintype "passive"))
      (node (ref "R124") (pin "1") (pinfunction "1_1") (pintype "passive"))
      (node (ref "R125") (pin "1") (pinfunction "1_1") (pintype "passive"))
      (node (ref "R126") (pin "1") (pinfunction "1_1") (pintype "passive"))
      (node (ref "R127") (pin "1") (pinfunction "1_1") (pintype "passive"))
      (node (ref "R128") (pin "1") (pinfunction "1_1") (pintype "passive"))
      (node (ref "R129") (pin "1") (pinfunction "1_1") (pintype "passive"))
      (node (ref "R136") (pin "1") (pinfunction "1_1") (pintype "passive"))
      (node (ref "R137") (pin "1") (pinfunction "1_1") (pintype "passive"))
      (node (ref "R48") (pin "2") (pinfunction "2_2") (pintype "passive"))
      (node (ref "R49") (pin "2") (pinfunction "2_2") (pintype "passive"))
      (node (ref "R51") (pin "2") (pinfunction "2_2") (pintype "passive"))
      (node (ref "U10") (pin "15") (pinfunction "CLK_INH_15") (pintype "input"))
      (node (ref "U10") (pin "8") (pinfunction "GND_8") (pintype "power_in"))
      (node (ref "U11") (pin "4") (pinfunction "GND_4") (pintype "passive"))
      (node (ref "U12") (pin "2") (pinfunction "K_2") (pintype "passive"))
      (node (ref "U12") (pin "3") (pinfunction "E_3") (pintype "passive"))
      (node (ref "U13") (pin "2") (pinfunction "K_2") (pintype "passive"))
      (node (ref "U13") (pin "3") (pinfunction "E_3") (pintype "passive"))
      (node (ref "U14") (pin "2") (pinfunction "K_2") (pintype "passive"))
      (node (ref "U14") (pin "3") (pinfunction "E_3") (pintype "passive"))
      (node (ref "U15") (pin "2") (pinfunction "K_2") (pintype "passive"))
      (node (ref "U15") (pin "3") (pinfunction "E_3") (pintype "passive"))
      (node (ref "U16") (pin "2") (pinfunction "K_2") (pintype "passive"))
      (node (ref "U16") (pin "3") (pinfunction "E_3") (pintype "passive"))
      (node (ref "U17") (pin "2") (pinfunction "K_2") (pintype "passive"))
      (node (ref "U17") (pin "3") (pinfunction "E_3") (pintype "passive"))
      (node (ref "U18") (pin "2") (pinfunction "K_2") (pintype "passive"))
      (node (ref "U18") (pin "3") (pinfunction "E_3") (pintype "passive"))
      (node (ref "U19") (pin "2") (pinfunction "K_2") (pintype "passive"))
      (node (ref "U19") (pin "3") (pinfunction "E_3") (pintype "passive"))
      (node (ref "U20") (pin "2") (pinfunction "K_2") (pintype "passive"))
      (node (ref "U20") (pin "3") (pinfunction "E_3") (pintype "passive"))
      (node (ref "U21") (pin "2") (pinfunction "K_2") (pintype "passive"))
      (node (ref "U21") (pin "3") (pinfunction "E_3") (pintype "passive"))
      (node (ref "U22") (pin "2") (pinfunction "K_2") (pintype "passive"))
      (node (ref "U22") (pin "3") (pinfunction "E_3") (pintype "passive"))
      (node (ref "U23") (pin "2") (pinfunction "K_2") (pintype "passive"))
      (node (ref "U23") (pin "3") (pinfunction "E_3") (pintype "passive"))
      (node (ref "U24") (pin "2") (pinfunction "K_2") (pintype "passive"))
      (node (ref "U24") (pin "3") (pinfunction "E_3") (pintype "passive"))
      (node (ref "U25") (pin "2") (pinfunction "K_2") (pintype "passive"))
      (node (ref "U25") (pin "3") (pinfunction "E_3") (pintype "passive"))
      (node (ref "U26") (pin "2") (pinfunction "K_2") (pintype "passive"))
      (node (ref "U26") (pin "3") (pinfunction "E_3") (pintype "passive"))
      (node (ref "U27") (pin "2") (pinfunction "K_2") (pintype "passive"))
      (node (ref "U27") (pin "3") (pinfunction "E_3") (pintype "passive"))
      (node (ref "U28") (pin "2") (pinfunction "K_2") (pintype "passive"))
      (node (ref "U28") (pin "3") (pinfunction "E_3") (pintype "passive"))
      (node (ref "U29") (pin "2") (pinfunction "K_2") (pintype "passive"))
      (node (ref "U29") (pin "3") (pinfunction "E_3") (pintype "passive"))
      (node (ref "U30") (pin "2") (pinfunction "K_2") (pintype "passive"))
      (node (ref "U30") (pin "3") (pinfunction "E_3") (pintype "passive"))
      (node (ref "U31") (pin "2") (pinfunction "K_2") (pintype "passive"))
      (node (ref "U31") (pin "3") (pinfunction "E_3") (pintype "passive"))
      (node (ref "U32") (pin "2") (pinfunction "K_2") (pintype "passive"))
      (node (ref "U32") (pin "3") (pinfunction "E_3") (pintype "passive"))
      (node (ref "U33") (pin "2") (pinfunction "K_2") (pintype "passive"))
      (node (ref "U33") (pin "3") (pinfunction "E_3") (pintype "passive"))
      (node (ref "U34") (pin "2") (pinfunction "K_2") (pintype "passive"))
      (node (ref "U34") (pin "3") (pinfunction "E_3") (pintype "passive"))
      (node (ref "U35") (pin "2") (pinfunction "K_2") (pintype "passive"))
      (node (ref "U35") (pin "3") (pinfunction "E_3") (pintype "passive"))
      (node (ref "U36") (pin "13") (pinfunction "~{OE}_13") (pintype "input"))
      (node (ref "U36") (pin "8") (pinfunction "GND_8") (pintype "power_in"))
      (node (ref "U8") (pin "15") (pinfunction "CLK_INH_15") (pintype "input"))
      (node (ref "U8") (pin "8") (pinfunction "GND_8") (pintype "power_in"))
      (node (ref "U9") (pin "15") (pinfunction "CLK_INH_15") (pintype "input"))
      (node (ref "U9") (pin "8") (pinfunction "GND_8") (pintype "power_in"))
    )
    (net (code "68") (name "Net-(C50-Pad1)") (class "Default")
      (node (ref "C50") (pin "1") (pinfunction "1_1") (pintype "passive"))
      (node (ref "R48") (pin "1") (pinfunction "1_1") (pintype "passive"))
    )
    (net (code "69") (name "Net-(D16-A)") (class "Default")
      (node (ref "D16") (pin "1") (pinfunction "A_1") (pintype "passive"))
      (node (ref "P12") (pin "1") (pinfunction "1_1") (pintype "passive"))
    )
    (net (code "70") (name "Net-(D17-PadK)") (class "Default")
      (node (ref "D17") (pin "K") (pinfunction "K_K") (pintype "passive"))
      (node (ref "R51") (pin "1") (pinfunction "1_1") (pintype "passive"))
    )
    (net (code "71") (name "Net-(D18-K)") (class "Default")
      (node (ref "C49") (pin "1") (pinfunction "1_1") (pintype "passive"))
      (node (ref "D18") (pin "2") (pinfunction "K_2") (pintype "passive"))
      (node (ref "L3") (pin "1") (pinfunction "1_1") (pintype "passive"))
      (node (ref "U11") (pin "3") (pinfunction "SW_3") (pintype "passive"))
    )
    (net (code "72") (name "Net-(D19-PadK)") (class "Default")
      (node (ref "D19") (pin "K") (pinfunction "K_K") (pintype "passive"))
      (node (ref "R60") (pin "1") (pinfunction "1_1") (pintype "passive"))
    )
    (net (code "73") (name "Net-(D20-PadK)") (class "Default")
      (node (ref "D20") (pin "K") (pinfunction "K_K") (pintype "passive"))
      (node (ref "R61") (pin "1") (pinfunction "1_1") (pintype "passive"))
    )
    (net (code "74") (name "Net-(D21-PadK)") (class "Default")
      (node (ref "D21") (pin "K") (pinfunction "K_K") (pintype "passive"))
      (node (ref "R62") (pin "1") (pinfunction "1_1") (pintype "passive"))
    )
    (net (code "75") (name "Net-(D22-PadK)") (class "Default")
      (node (ref "D22") (pin "K") (pinfunction "K_K") (pintype "passive"))
      (node (ref "R63") (pin "1") (pinfunction "1_1") (pintype "passive"))
    )
    (net (code "76") (name "Net-(D23-PadK)") (class "Default")
      (node (ref "D23") (pin "K") (pinfunction "K_K") (pintype "passive"))
      (node (ref "R64") (pin "1") (pinfunction "1_1") (pintype "passive"))
    )
    (net (code "77") (name "Net-(D24-PadK)") (class "Default")
      (node (ref "D24") (pin "K") (pinfunction "K_K") (pintype "passive"))
      (node (ref "R65") (pin "1") (pinfunction "1_1") (pintype "passive"))
    )
    (net (code "78") (name "Net-(D25-PadK)") (class "Default")
      (node (ref "D25") (pin "K") (pinfunction "K_K") (pintype "passive"))
      (node (ref "R66") (pin "1") (pinfunction "1_1") (pintype "passive"))
    )
    (net (code "79") (name "Net-(D26-PadK)") (class "Default")
      (node (ref "D26") (pin "K") (pinfunction "K_K") (pintype "passive"))
      (node (ref "R67") (pin "1") (pinfunction "1_1") (pintype "passive"))
    )
    (net (code "80") (name "Net-(D27-PadK)") (class "Default")
      (node (ref "D27") (pin "K") (pinfunction "K_K") (pintype "passive"))
      (node (ref "R84") (pin "1") (pinfunction "1_1") (pintype "passive"))
    )
    (net (code "81") (name "Net-(D28-PadK)") (class "Default")
      (node (ref "D28") (pin "K") (pinfunction "K_K") (pintype "passive"))
      (node (ref "R85") (pin "1") (pinfunction "1_1") (pintype "passive"))
    )
    (net (code "82") (name "Net-(D29-PadK)") (class "Default")
      (node (ref "D29") (pin "K") (pinfunction "K_K") (pintype "passive"))
      (node (ref "R86") (pin "1") (pinfunction "1_1") (pintype "passive"))
    )
    (net (code "83") (name "Net-(D30-PadK)") (class "Default")
      (node (ref "D30") (pin "K") (pinfunction "K_K") (pintype "passive"))
      (node (ref "R87") (pin "1") (pinfunction "1_1") (pintype "passive"))
    )
    (net (code "84") (name "Net-(D31-PadK)") (class "Default")
      (node (ref "D31") (pin "K") (pinfunction "K_K") (pintype "passive"))
      (node (ref "R88") (pin "1") (pinfunction "1_1") (pintype "passive"))
    )
    (net (code "85") (name "Net-(D32-PadK)") (class "Default")
      (node (ref "D32") (pin "K") (pinfunction "K_K") (pintype "passive"))
      (node (ref "R89") (pin "1") (pinfunction "1_1") (pintype "passive"))
    )
    (net (code "86") (name "Net-(D33-PadK)") (class "Default")
      (node (ref "D33") (pin "K") (pinfunction "K_K") (pintype "passive"))
      (node (ref "R90") (pin "1") (pinfunction "1_1") (pintype "passive"))
    )
    (net (code "87") (name "Net-(D34-PadK)") (class "Default")
      (node (ref "D34") (pin "K") (pinfunction "K_K") (pintype "passive"))
      (node (ref "R91") (pin "1") (pinfunction "1_1") (pintype "passive"))
    )
    (net (code "88") (name "Net-(D35-PadK)") (class "Default")
      (node (ref "D35") (pin "K") (pinfunction "K_K") (pintype "passive"))
      (node (ref "R108") (pin "1") (pinfunction "1_1") (pintype "passive"))
    )
    (net (code "89") (name "Net-(D36-PadK)") (class "Default")
      (node (ref "D36") (pin "K") (pinfunction "K_K") (pintype "passive"))
      (node (ref "R109") (pin "1") (pinfunction "1_1") (pintype "passive"))
    )
    (net (code "90") (name "Net-(D37-PadK)") (class "Default")
      (node (ref "D37") (pin "K") (pinfunction "K_K") (pintype "passive"))
      (node (ref "R110") (pin "1") (pinfunction "1_1") (pintype "passive"))
    )
    (net (code "91") (name "Net-(D38-PadK)") (class "Default")
      (node (ref "D38") (pin "K") (pinfunction "K_K") (pintype "passive"))
      (node (ref "R111") (pin "1") (pinfunction "1_1") (pintype "passive"))
    )
    (net (code "92") (name "Net-(D39-PadK)") (class "Default")
      (node (ref "D39") (pin "K") (pinfunction "K_K") (pintype "passive"))
      (node (ref "R112") (pin "1") (pinfunction "1_1") (pintype "passive"))
    )
    (net (code "93") (name "Net-(D40-PadK)") (class "Default")
      (node (ref "D40") (pin "K") (pinfunction "K_K") (pintype "passive"))
      (node (ref "R113") (pin "1") (pinfunction "1_1") (pintype "passive"))
    )
    (net (code "94") (name "Net-(D41-PadK)") (class "Default")
      (node (ref "D41") (pin "K") (pinfunction "K_K") (pintype "passive"))
      (node (ref "R114") (pin "1") (pinfunction "1_1") (pintype "passive"))
    )
    (net (code "95") (name "Net-(D42-PadK)") (class "Default")
      (node (ref "D42") (pin "K") (pinfunction "K_K") (pintype "passive"))
      (node (ref "R115") (pin "1") (pinfunction "1_1") (pintype "passive"))
    )
    (net (code "96") (name "Net-(D43-A)") (class "Default")
      (node (ref "D43") (pin "1") (pinfunction "A_1") (pintype "passive"))
      (node (ref "K3") (pin "1") (pinfunction "1_1") (pintype "passive"))
      (node (ref "Q13") (pin "3") (pinfunction "C_3") (pintype "passive"))
    )
    (net (code "97") (name "Net-(D44-A)") (class "Default")
      (node (ref "D44") (pin "1") (pinfunction "A_1") (pintype "passive"))
      (node (ref "K4") (pin "1") (pinfunction "1_1") (pintype "passive"))
      (node (ref "Q14") (pin "3") (pinfunction "C_3") (pintype "passive"))
    )
    (net (code "98") (name "Net-(D45-A)") (class "Default")
      (node (ref "D45") (pin "1") (pinfunction "A_1") (pintype "passive"))
      (node (ref "K5") (pin "1") (pinfunction "1_1") (pintype "passive"))
      (node (ref "Q15") (pin "3") (pinfunction "C_3") (pintype "passive"))
    )
    (net (code "99") (name "Net-(D46-A)") (class "Default")
      (node (ref "D46") (pin "1") (pinfunction "A_1") (pintype "passive"))
      (node (ref "K6") (pin "1") (pinfunction "1_1") (pintype "passive"))
      (node (ref "Q16") (pin "3") (pinfunction "C_3") (pintype "passive"))
    )
    (net (code "100") (name "Net-(D47-A)") (class "Default")
      (node (ref "D47") (pin "1") (pinfunction "A_1") (pintype "passive"))
      (node (ref "K7") (pin "1") (pinfunction "1_1") (pintype "passive"))
      (node (ref "Q17") (pin "3") (pinfunction "C_3") (pintype "passive"))
    )
    (net (code "101") (name "Net-(D48-A)") (class "Default")
      (node (ref "D48") (pin "1") (pinfunction "A_1") (pintype "passive"))
      (node (ref "K8") (pin "1") (pinfunction "1_1") (pintype "passive"))
      (node (ref "Q18") (pin "3") (pinfunction "C_3") (pintype "passive"))
    )
    (net (code "102") (name "Net-(D49-PadK)") (class "Default")
      (node (ref "D49") (pin "K") (pinfunction "K_K") (pintype "passive"))
      (node (ref "R124") (pin "2") (pinfunction "2_2") (pintype "passive"))
    )
    (net (code "103") (name "Net-(D50-PadK)") (class "Default")
      (node (ref "D50") (pin "K") (pinfunction "K_K") (pintype "passive"))
      (node (ref "R125") (pin "2") (pinfunction "2_2") (pintype "passive"))
    )
    (net (code "104") (name "Net-(D51-PadK)") (class "Default")
      (node (ref "D51") (pin "K") (pinfunction "K_K") (pintype "passive"))
      (node (ref "R126") (pin "2") (pinfunction "2_2") (pintype "passive"))
    )
    (net (code "105") (name "Net-(D52-PadK)") (class "Default")
      (node (ref "D52") (pin "K") (pinfunction "K_K") (pintype "passive"))
      (node (ref "R127") (pin "2") (pinfunction "2_2") (pintype "passive"))
    )
    (net (code "106") (name "Net-(D53-PadK)") (class "Default")
      (node (ref "D53") (pin "K") (pinfunction "K_K") (pintype "passive"))
      (node (ref "R128") (pin "2") (pinfunction "2_2") (pintype "passive"))
    )
    (net (code "107") (name "Net-(D54-PadK)") (class "Default")
      (node (ref "D54") (pin "K") (pinfunction "K_K") (pintype "passive"))
      (node (ref "R129") (pin "2") (pinfunction "2_2") (pintype "passive"))
    )
    (net (code "108") (name "Net-(D55-A)") (class "Default")
      (node (ref "D55") (pin "1") (pinfunction "A_1") (pintype "passive"))
      (node (ref "K9") (pin "1") (pinfunction "1_1") (pintype "passive"))
      (node (ref "Q19") (pin "3") (pinfunction "C_3") (pintype "passive"))
    )
    (net (code "109") (name "Net-(D56-A)") (class "Default")
      (node (ref "D56") (pin "1") (pinfunction "A_1") (pintype "passive"))
      (node (ref "K10") (pin "1") (pinfunction "1_1") (pintype "passive"))
      (node (ref "Q20") (pin "3") (pinfunction "C_3") (pintype "passive"))
    )
    (net (code "110") (name "Net-(D57-PadK)") (class "Default")
      (node (ref "D57") (pin "K") (pinfunction "K_K") (pintype "passive"))
      (node (ref "R136") (pin "2") (pinfunction "2_2") (pintype "passive"))
    )
    (net (code "111") (name "Net-(D58-PadK)") (class "Default")
      (node (ref "D58") (pin "K") (pinfunction "K_K") (pintype "passive"))
      (node (ref "R137") (pin "2") (pinfunction "2_2") (pintype "passive"))
    )
    (net (code "112") (name "Net-(K3-Pad3)") (class "Default")
      (node (ref "K3") (pin "3") (pinfunction "3_3") (pintype "passive"))
      (node (ref "P24") (pin "2") (pinfunction "2_2") (pintype "passive"))
    )
    (net (code "113") (name "Net-(K4-Pad3)") (class "Default")
      (node (ref "K4") (pin "3") (pinfunction "3_3") (pintype "passive"))
      (node (ref "P25") (pin "2") (pinfunction "2_2") (pintype "passive"))
    )
    (net (code "114") (name "Net-(K5-Pad3)") (class "Default")
      (node (ref "K5") (pin "3") (pinfunction "3_3") (pintype "passive"))
      (node (ref "P26") (pin "2") (pinfunction "2_2") (pintype "passive"))
    )
    (net (code "115") (name "Net-(K6-Pad3)") (class "Default")
      (node (ref "K6") (pin "3") (pinfunction "3_3") (pintype "passive"))
      (node (ref "P27") (pin "2") (pinfunction "2_2") (pintype "passive"))
    )
    (net (code "116") (name "Net-(K7-Pad3)") (class "Default")
      (node (ref "K7") (pin "3") (pinfunction "3_3") (pintype "passive"))
      (node (ref "P28") (pin "2") (pinfunction "2_2") (pintype "passive"))
    )
    (net (code "117") (name "Net-(K8-Pad3)") (class "Default")
      (node (ref "K8") (pin "3") (pinfunction "3_3") (pintype "passive"))
      (node (ref "P29") (pin "2") (pinfunction "2_2") (pintype "passive"))
    )
    (net (code "118") (name "Net-(K9-Pad3)") (class "Default")
      (node (ref "K9") (pin "3") (pinfunction "3_3") (pintype "passive"))
      (node (ref "P30") (pin "2") (pinfunction "2_2") (pintype "passive"))
    )
    (net (code "119") (name "Net-(K10-Pad3)") (class "Default")
      (node (ref "K10") (pin "3") (pinfunction "3_3") (pintype "passive"))
      (node (ref "P31") (pin "2") (pinfunction "2_2") (pintype "passive"))
    )
    (net (code "120") (name "Net-(Q13-B)") (class "Default")
      (node (ref "Q13") (pin "1") (pinfunction "B_1") (pintype "passive"))
      (node (ref "R130") (pin "2") (pinfunction "2_2") (pintype "passive"))
    )
    (net (code "121") (name "Net-(Q14-B)") (class "Default")
      (node (ref "Q14") (pin "1") (pinfunction "B_1") (pintype "passive"))
      (node (ref "R131") (pin "2") (pinfunction "2_2") (pintype "passive"))
    )
    (net (code "122") (name "Net-(Q15-B)") (class "Default")
      (node (ref "Q15") (pin "1") (pinfunction "B_1") (pintype "passive"))
      (node (ref "R132") (pin "2") (pinfunction "2_2") (pintype "passive"))
    )
    (net (code "123") (name "Net-(Q16-B)") (class "Default")
      (node (ref "Q16") (pin "1") (pinfunction "B_1") (pintype "passive"))
      (node (ref "R133") (pin "2") (pinfunction "2_2") (pintype "passive"))
    )
    (net (code "124") (name "Net-(Q17-B)") (class "Default")
      (node (ref "Q17") (pin "1") (pinfunction "B_1") (pintype "passive"))
      (node (ref "R134") (pin "2") (pinfunction "2_2") (pintype "passive"))
    )
    (net (code "125") (name "Net-(Q18-B)") (class "Default")
      (node (ref "Q18") (pin "1") (pinfunction "B_1") (pintype "passive"))
      (node (ref "R135") (pin "2") (pinfunction "2_2") (pintype "passive"))
    )
    (net (code "126") (name "Net-(Q19-B)") (class "Default")
      (node (ref "Q19") (pin "1") (pinfunction "B_1") (pintype "passive"))
      (node (ref "R138") (pin "2") (pinfunction "2_2") (pintype "passive"))
    )
    (net (code "127") (name "Net-(Q20-B)") (class "Default")
      (node (ref "Q20") (pin "1") (pinfunction "B_1") (pintype "passive"))
      (node (ref "R139") (pin "2") (pinfunction "2_2") (pintype "passive"))
    )
    (net (code "128") (name "Net-(U8-QH)") (class "Default")
      (node (ref "U8") (pin "9") (pinfunction "QH_9") (pintype "output"))
      (node (ref "U9") (pin "10") (pinfunction "SI_10") (pintype "input"))
    )
    (net (code "129") (name "Net-(U10-SI)") (class "Default")
      (node (ref "U10") (pin "10") (pinfunction "SI_10") (pintype "input"))
      (node (ref "U9") (pin "9") (pinfunction "QH_9") (pintype "output"))
    )
    (net (code "130") (name "Net-(U11-BS)") (class "Default")
      (node (ref "C49") (pin "2") (pinfunction "2_2") (pintype "passive"))
      (node (ref "U11") (pin "1") (pinfunction "BS_1") (pintype "passive"))
    )
    (net (code "131") (name "Net-(U11-COMP)") (class "Default")
      (node (ref "C50") (pin "2") (pinfunction "2_2") (pintype "passive"))
      (node (ref "U11") (pin "6") (pinfunction "COMP_6") (pintype "passive"))
    )
    (net (code "132") (name "Net-(U11-EN)") (class "Default")
      (node (ref "R47") (pin "2") (pinfunction "2_2") (pintype "passive"))
      (node (ref "U11") (pin "7") (pinfunction "EN_7") (pintype "passive"))
    )
    (net (code "133") (name "Net-(U11-FB)") (class "Default")
      (node (ref "R49") (pin "1") (pinfunction "1_1") (pintype "passive"))
      (node (ref "R50") (pin "1") (pinfunction "1_1") (pintype "passive"))
      (node (ref "U11") (pin "5") (pinfunction "FB_5") (pintype "passive"))
    )
    (net (code "134") (name "Net-(U11-SS)") (class "Default")
      (node (ref "C48") (pin "2") (pinfunction "2_2") (pintype "passive"))
      (node (ref "U11") (pin "8") (pinfunction "SS_8") (pintype "passive"))
    )
    (net (code "135") (name "Net-(U12-A)") (class "Default")
      (node (ref "R68") (pin "2") (pinfunction "2_2") (pintype "passive"))
      (node (ref "U12") (pin "1") (pinfunction "A_1") (pintype "passive"))
    )
    (net (code "136") (name "Net-(U13-A)") (class "Default")
      (node (ref "R69") (pin "2") (pinfunction "2_2") (pintype "passive"))
      (node (ref "U13") (pin "1") (pinfunction "A_1") (pintype "passive"))
    )
    (net (code "137") (name "Net-(U14-A)") (class "Default")
      (node (ref "R70") (pin "2") (pinfunction "2_2") (pintype "passive"))
      (node (ref "U14") (pin "1") (pinfunction "A_1") (pintype "passive"))
    )
    (net (code "138") (name "Net-(U15-A)") (class "Default")
      (node (ref "R71") (pin "2") (pinfunction "2_2") (pintype "passive"))
      (node (ref "U15") (pin "1") (pinfunction "A_1") (pintype "passive"))
    )
    (net (code "139") (name "Net-(U16-A)") (class "Default")
      (node (ref "R72") (pin "2") (pinfunction "2_2") (pintype "passive"))
      (node (ref "U16") (pin "1") (pinfunction "A_1") (pintype "passive"))
    )
    (net (code "140") (name "Net-(U17-A)") (class "Default")
      (node (ref "R73") (pin "2") (pinfunction "2_2") (pintype "passive"))
      (node (ref "U17") (pin "1") (pinfunction "A_1") (pintype "passive"))
    )
    (net (code "141") (name "Net-(U18-A)") (class "Default")
      (node (ref "R74") (pin "2") (pinfunction "2_2") (pintype "passive"))
      (node (ref "U18") (pin "1") (pinfunction "A_1") (pintype "passive"))
    )
    (net (code "142") (name "Net-(U19-A)") (class "Default")
      (node (ref "R75") (pin "2") (pinfunction "2_2") (pintype "passive"))
      (node (ref "U19") (pin "1") (pinfunction "A_1") (pintype "passive"))
    )
    (net (code "143") (name "Net-(U20-A)") (class "Default")
      (node (ref "R92") (pin "2") (pinfunction "2_2") (pintype "passive"))
      (node (ref "U20") (pin "1") (pinfunction "A_1") (pintype "passive"))
    )
    (net (code "144") (name "Net-(U21-A)") (class "Default")
      (node (ref "R93") (pin "2") (pinfunction "2_2") (pintype "passive"))
      (node (ref "U21") (pin "1") (pinfunction "A_1") (pintype "passive"))
    )
    (net (code "145") (name "Net-(U22-A)") (class "Default")
      (node (ref "R94") (pin "2") (pinfunction "2_2") (pintype "passive"))
      (node (ref "U22") (pin "1") (pinfunction "A_1") (pintype "passive"))
    )
    (net (code "146") (name "Net-(U23-A)") (class "Default")
      (node (ref "R95") (pin "2") (pinfunction "2_2") (pintype "passive"))
      (node (ref "U23") (pin "1") (pinfunction "A_1") (pintype "passive"))
    )
    (net (code "147") (name "Net-(U24-A)") (class "Default")
      (node (ref "R96") (pin "2") (pinfunction "2_2") (pintype "passive"))
      (node (ref "U24") (pin "1") (pinfunction "A_1") (pintype "passive"))
    )
    (net (code "148") (name "Net-(U25-A)") (class "Default")
      (node (ref "R97") (pin "2") (pinfunction "2_2") (pintype "passive"))
      (node (ref "U25") (pin "1") (pinfunction "A_1") (pintype "passive"))
    )
    (net (code "149") (name "Net-(U26-A)") (class "Default")
      (node (ref "R98") (pin "2") (pinfunction "2_2") (pintype "passive"))
      (node (ref "U26") (pin "1") (pinfunction "A_1") (pintype "passive"))
    )
    (net (code "150") (name "Net-(U27-A)") (class "Default")
      (node (ref "R99") (pin "2") (pinfunction "2_2") (pintype "passive"))
      (node (ref "U27") (pin "1") (pinfunction "A_1") (pintype "passive"))
    )
    (net (code "151") (name "Net-(U28-A)") (class "Default")
      (node (ref "R116") (pin "2") (pinfunction "2_2") (pintype "passive"))
      (node (ref "U28") (pin "1") (pinfunction "A_1") (pintype "passive"))
    )
    (net (code "152") (name "Net-(U29-A)") (class "Default")
      (node (ref "R117") (pin "2") (pinfunction "2_2") (pintype "passive"))
      (node (ref "U29") (pin "1") (pinfunction "A_1") (pintype "passive"))
    )
    (net (code "153") (name "Net-(U30-A)") (class "Default")
      (node (ref "R118") (pin "2") (pinfunction "2_2") (pintype "passive"))
      (node (ref "U30") (pin "1") (pinfunction "A_1") (pintype "passive"))
    )
    (net (code "154") (name "Net-(U31-A)") (class "Default")
      (node (ref "R119") (pin "2") (pinfunction "2_2") (pintype "passive"))
      (node (ref "U31") (pin "1") (pinfunction "A_1") (pintype "passive"))
    )
    (net (code "155") (name "Net-(U32-A)") (class "Default")
      (node (ref "R120") (pin "2") (pinfunction "2_2") (pintype "passive"))
      (node (ref "U32") (pin "1") (pinfunction "A_1") (pintype "passive"))
    )
    (net (code "156") (name "Net-(U33-A)") (class "Default")
      (node (ref "R121") (pin "2") (pinfunction "2_2") (pintype "passive"))
      (node (ref "U33") (pin "1") (pinfunction "A_1") (pintype "passive"))
    )
    (net (code "157") (name "Net-(U34-A)") (class "Default")
      (node (ref "R122") (pin "2") (pinfunction "2_2") (pintype "passive"))
      (node (ref "U34") (pin "1") (pinfunction "A_1") (pintype "passive"))
    )
    (net (code "158") (name "Net-(U35-A)") (class "Default")
      (node (ref "R123") (pin "2") (pinfunction "2_2") (pintype "passive"))
      (node (ref "U35") (pin "1") (pinfunction "A_1") (pintype "passive"))
    )
    (net (code "159") (name "unconnected-(HOLES1-Pad1)") (class "Default")
      (node (ref "HOLES1") (pin "1") (pinfunction "1_1") (pintype "passive"))
    )
    (net (code "160") (name "unconnected-(HOLES2-Pad1)") (class "Default")
      (node (ref "HOLES2") (pin "1") (pinfunction "1_1") (pintype "passive"))
    )
    (net (code "161") (name "unconnected-(HOLES3-Pad1)") (class "Default")
      (node (ref "HOLES3") (pin "1") (pinfunction "1_1") (pintype "passive"))
    )
    (net (code "162") (name "unconnected-(HOLES4-Pad1)") (class "Default")
      (node (ref "HOLES4") (pin "1") (pinfunction "1_1") (pintype "passive"))
    )
    (net (code "163") (name "unconnected-(U8-~{QH}-Pad7)") (class "Default")
      (node (ref "U8") (pin "7") (pinfunction "~{QH}_7") (pintype "output"))
    )
    (net (code "164") (name "unconnected-(U9-~{QH}-Pad7)") (class "Default")
      (node (ref "U9") (pin "7") (pinfunction "~{QH}_7") (pintype "output"))
    )
    (net (code "165") (name "unconnected-(U10-~{QH}-Pad7)") (class "Default")
      (node (ref "U10") (pin "7") (pinfunction "~{QH}_7") (pintype "output"))
    )
  )
)
